# controller.net
KiCad netlist of a schematic drawn in EasyEDA Pro
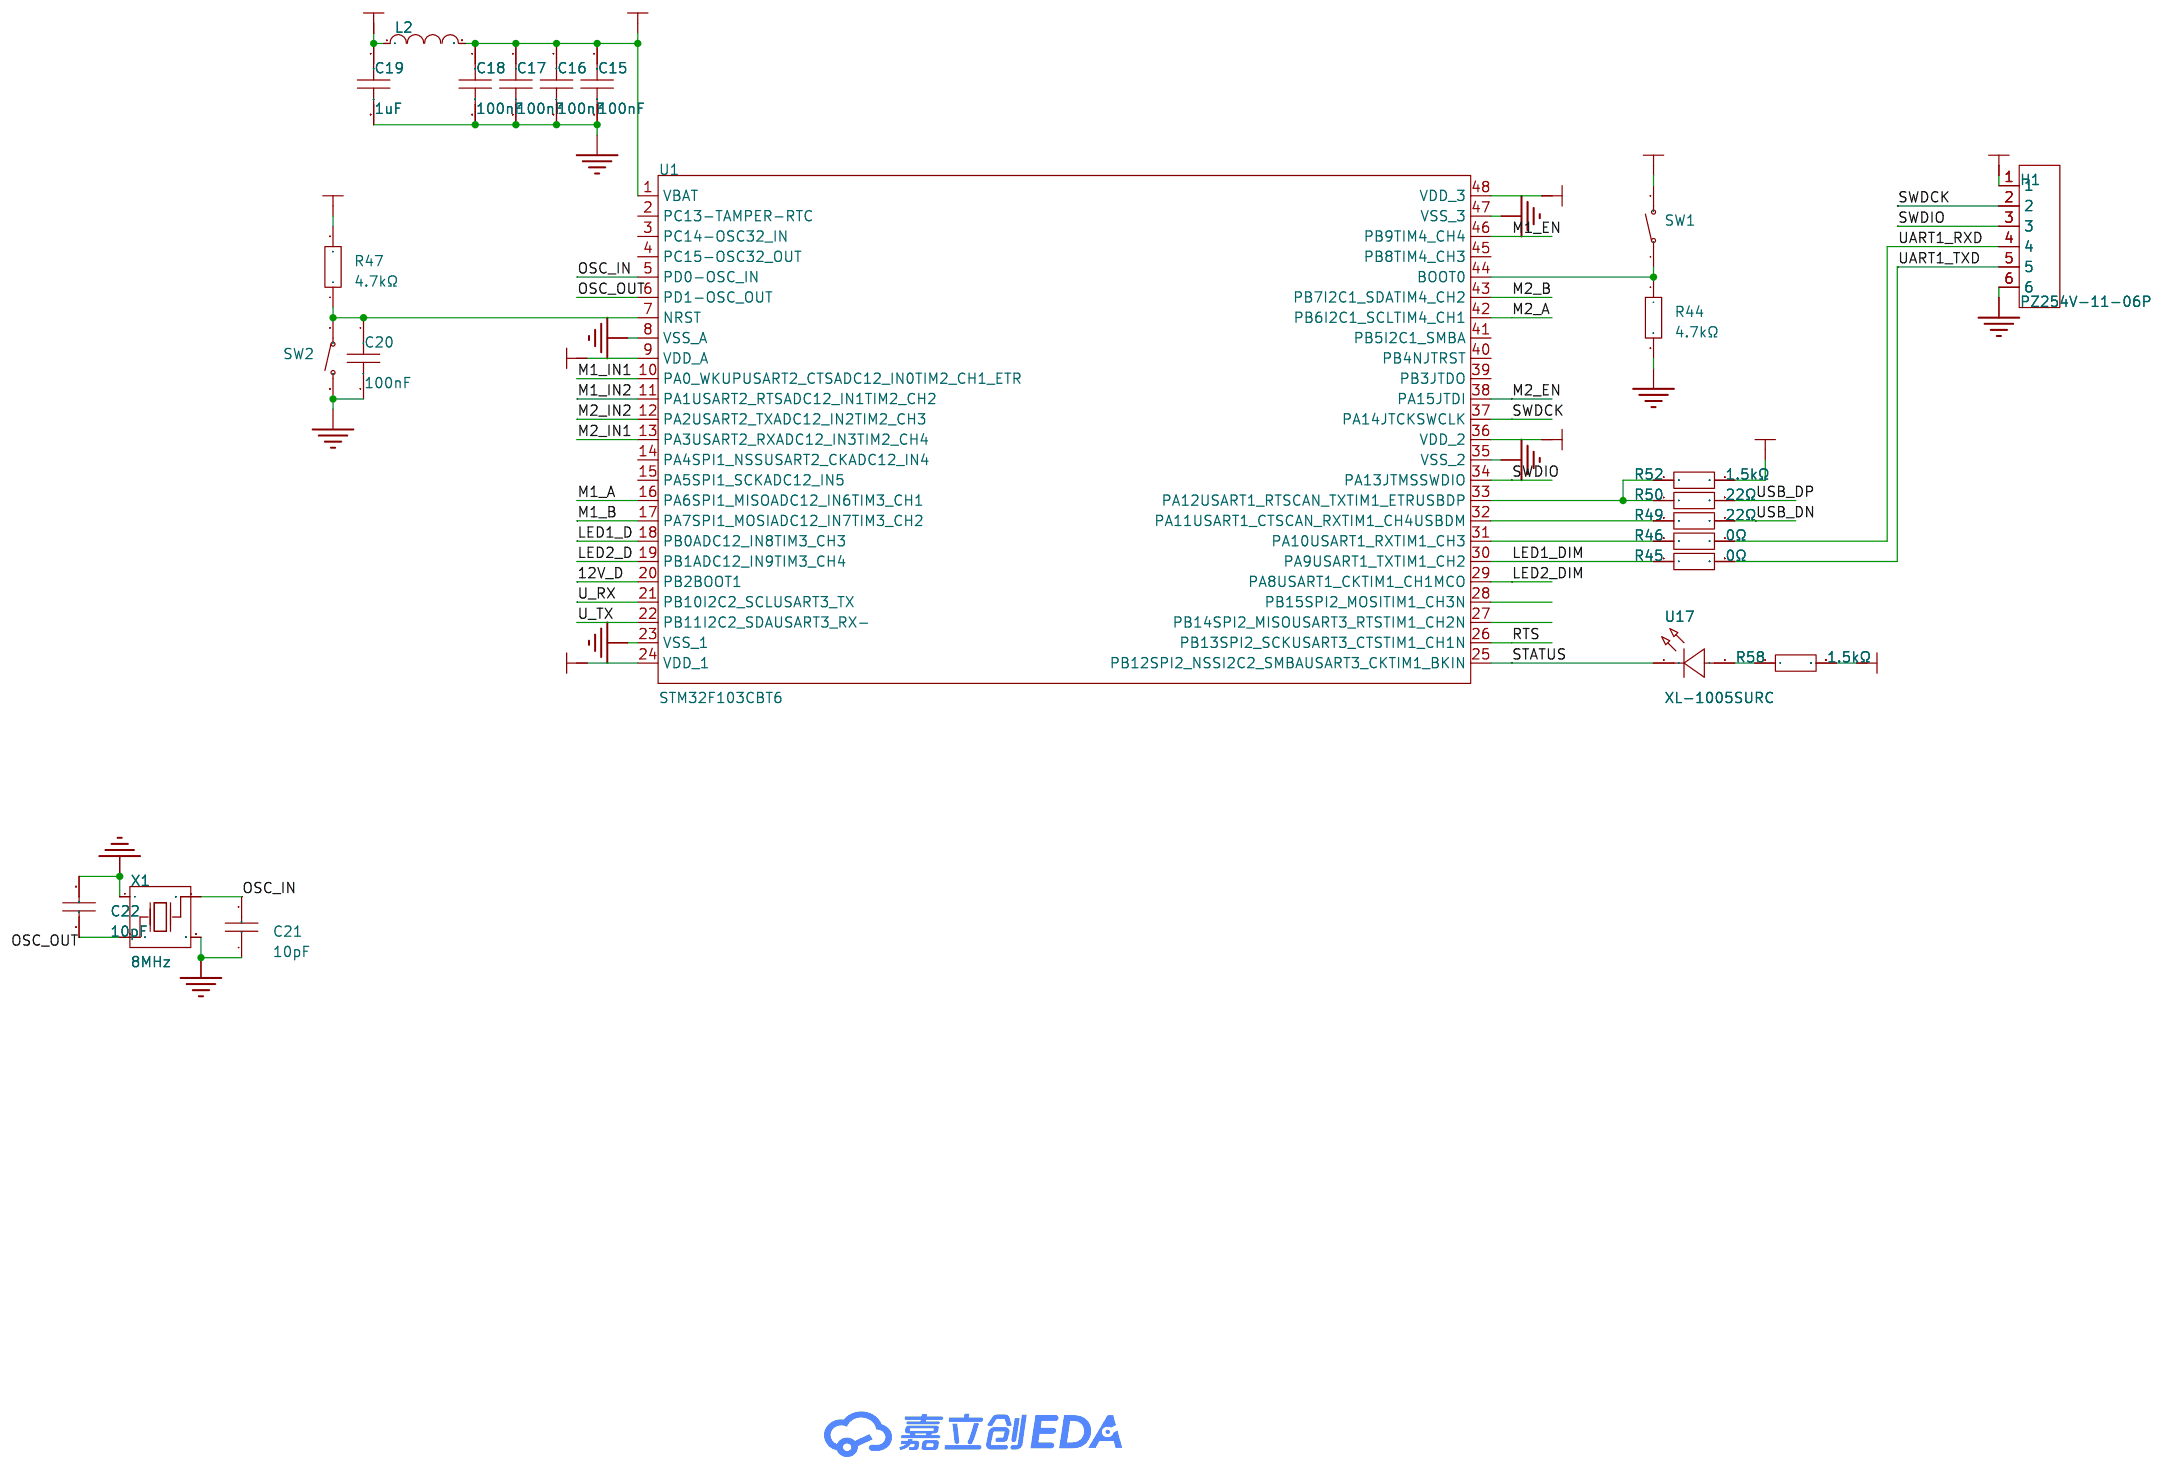
[diagram p0: mcu]
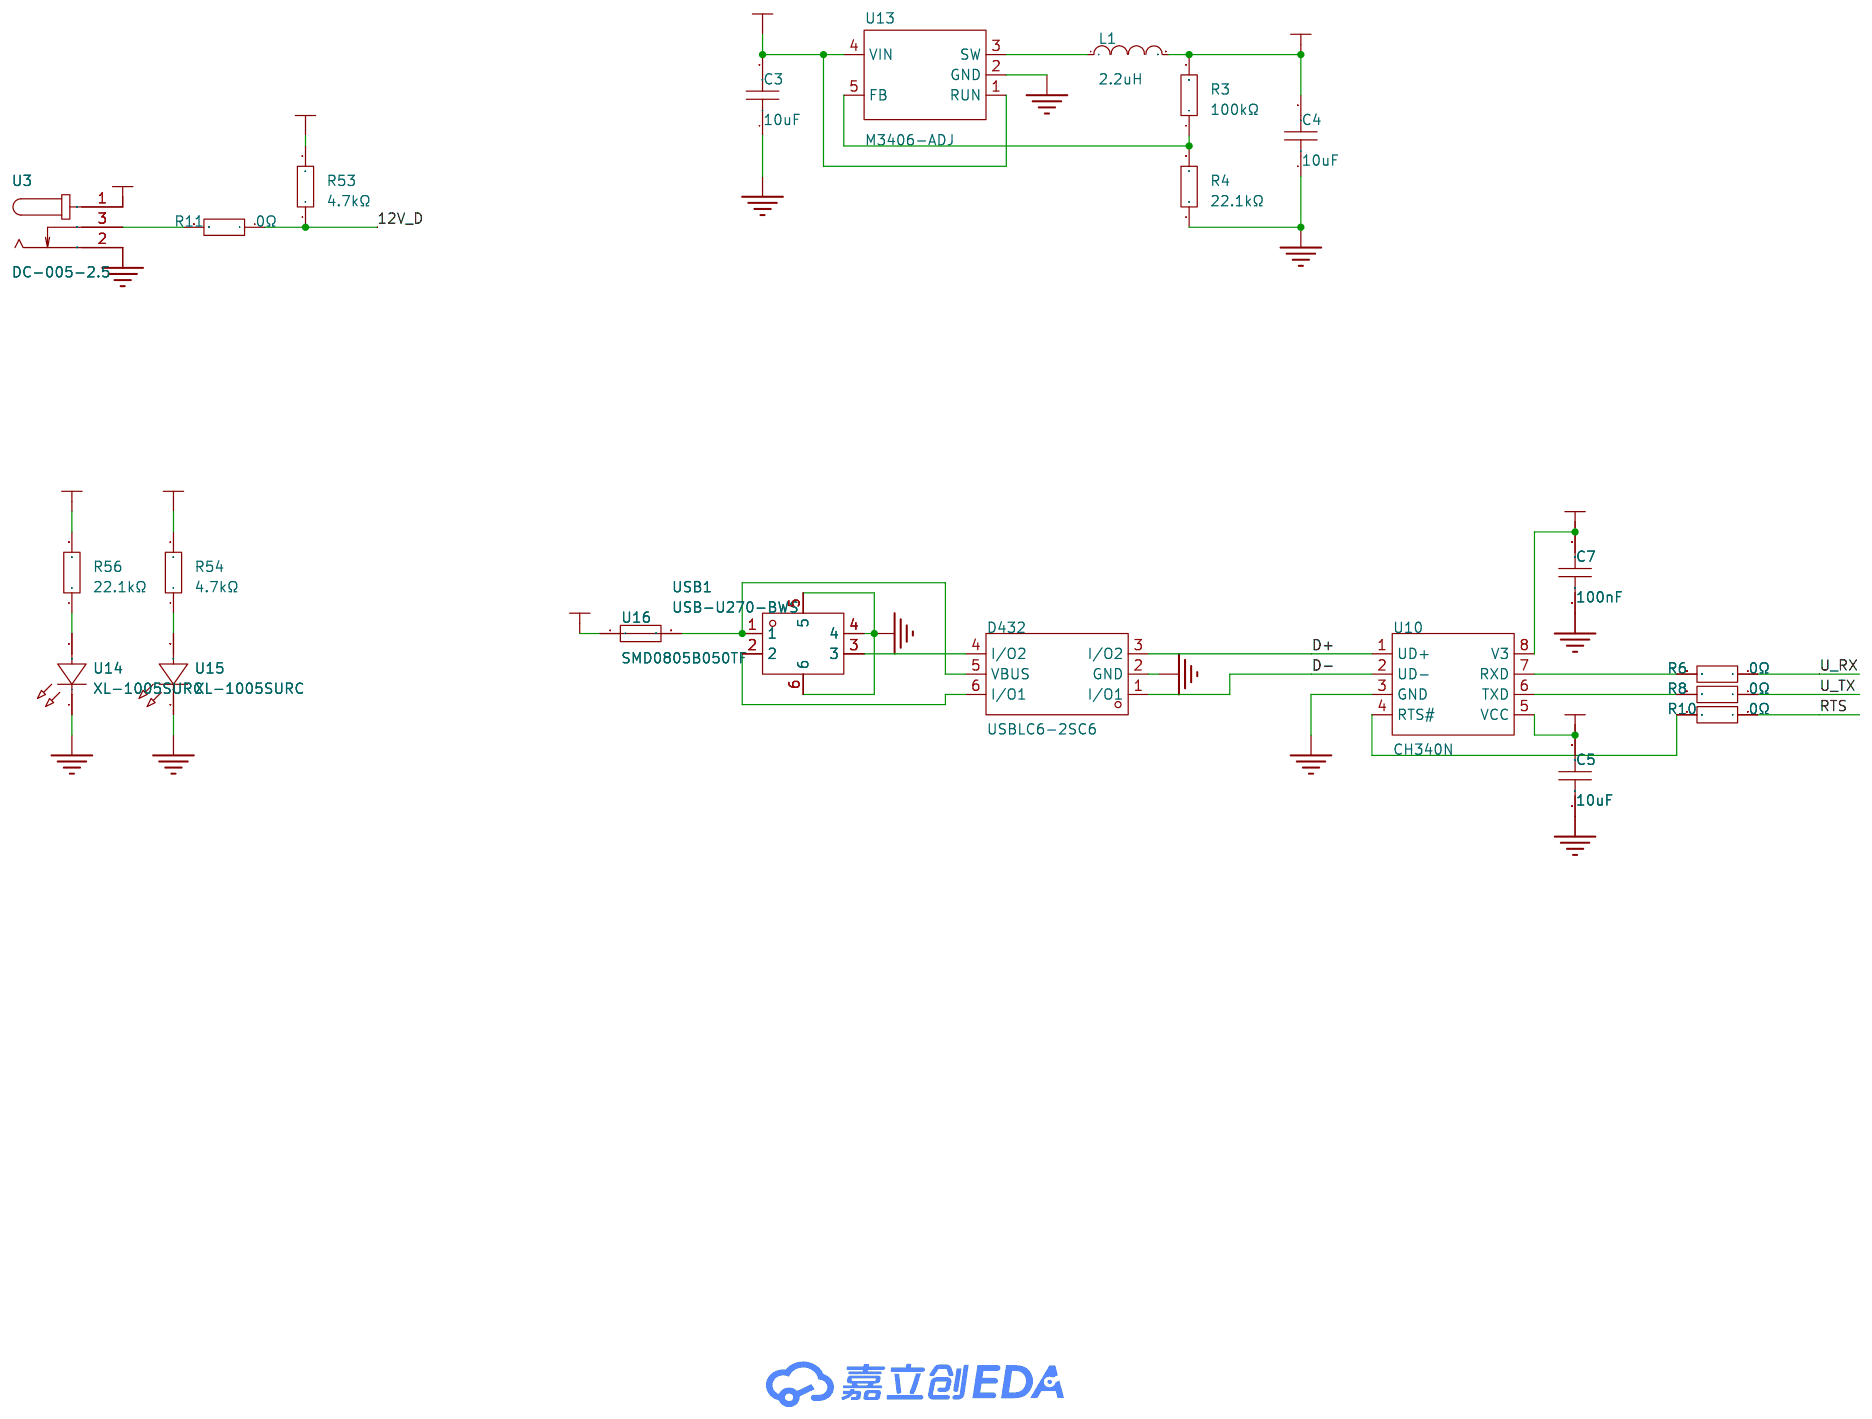
[diagram p1: power]
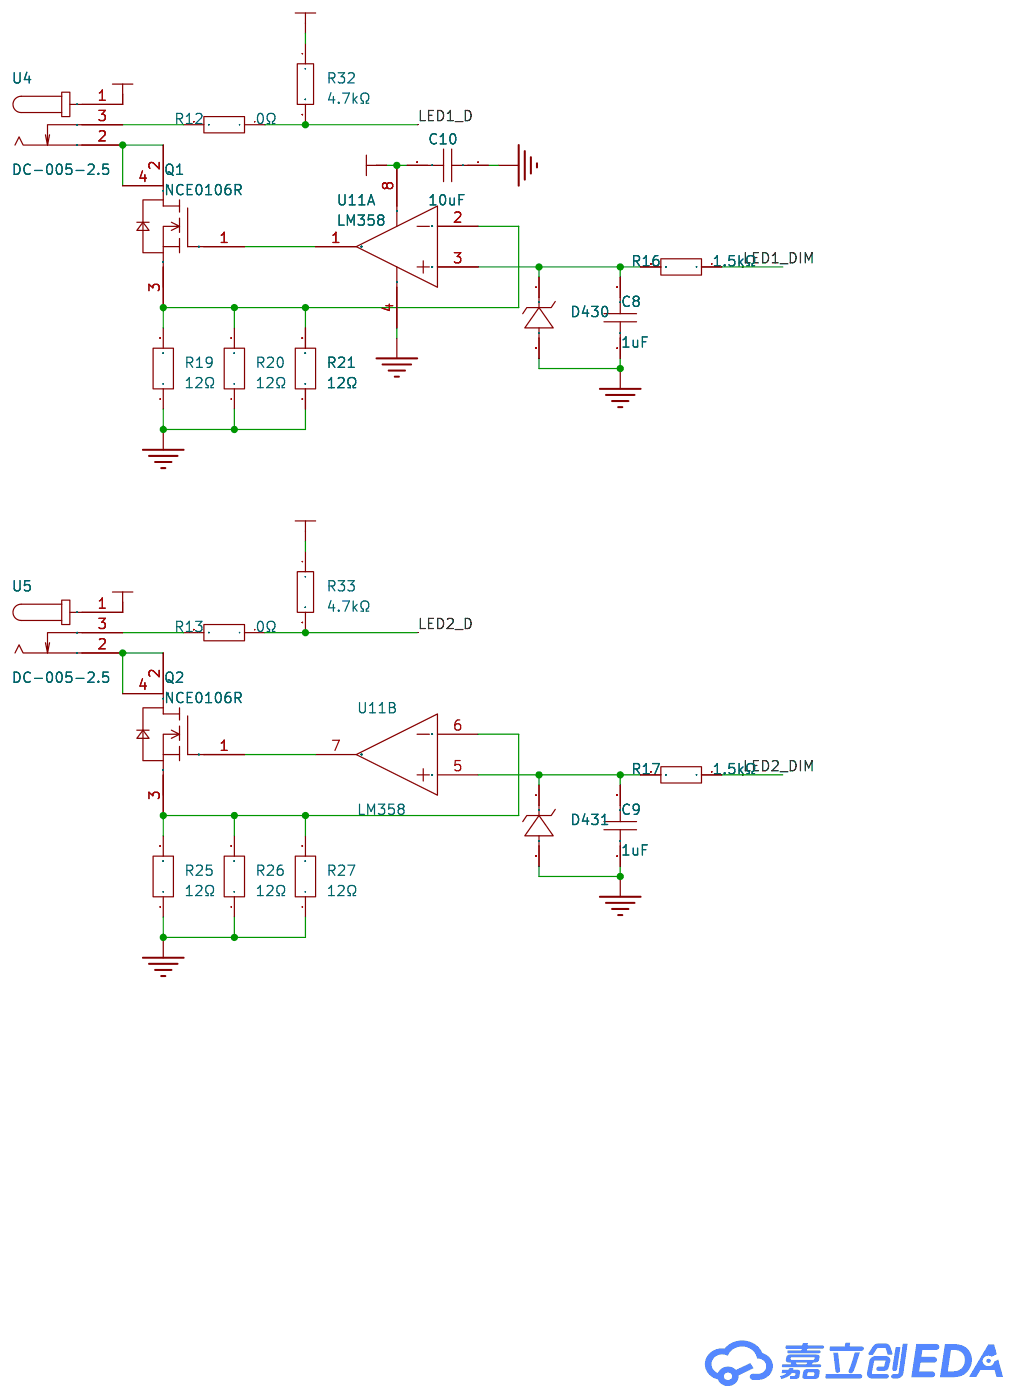
[diagram p2: led]
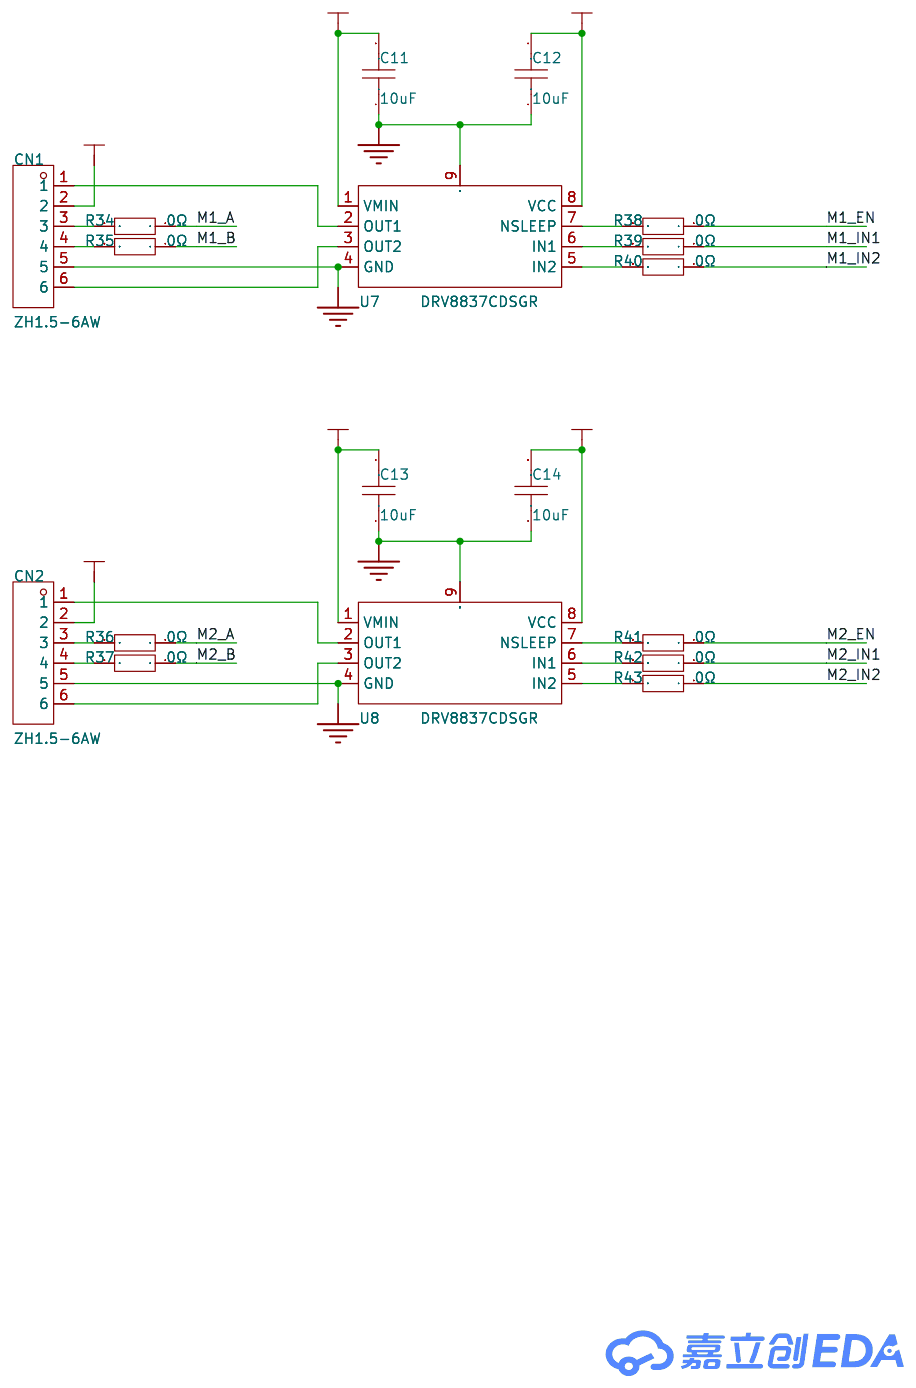
[diagram p3: motor]
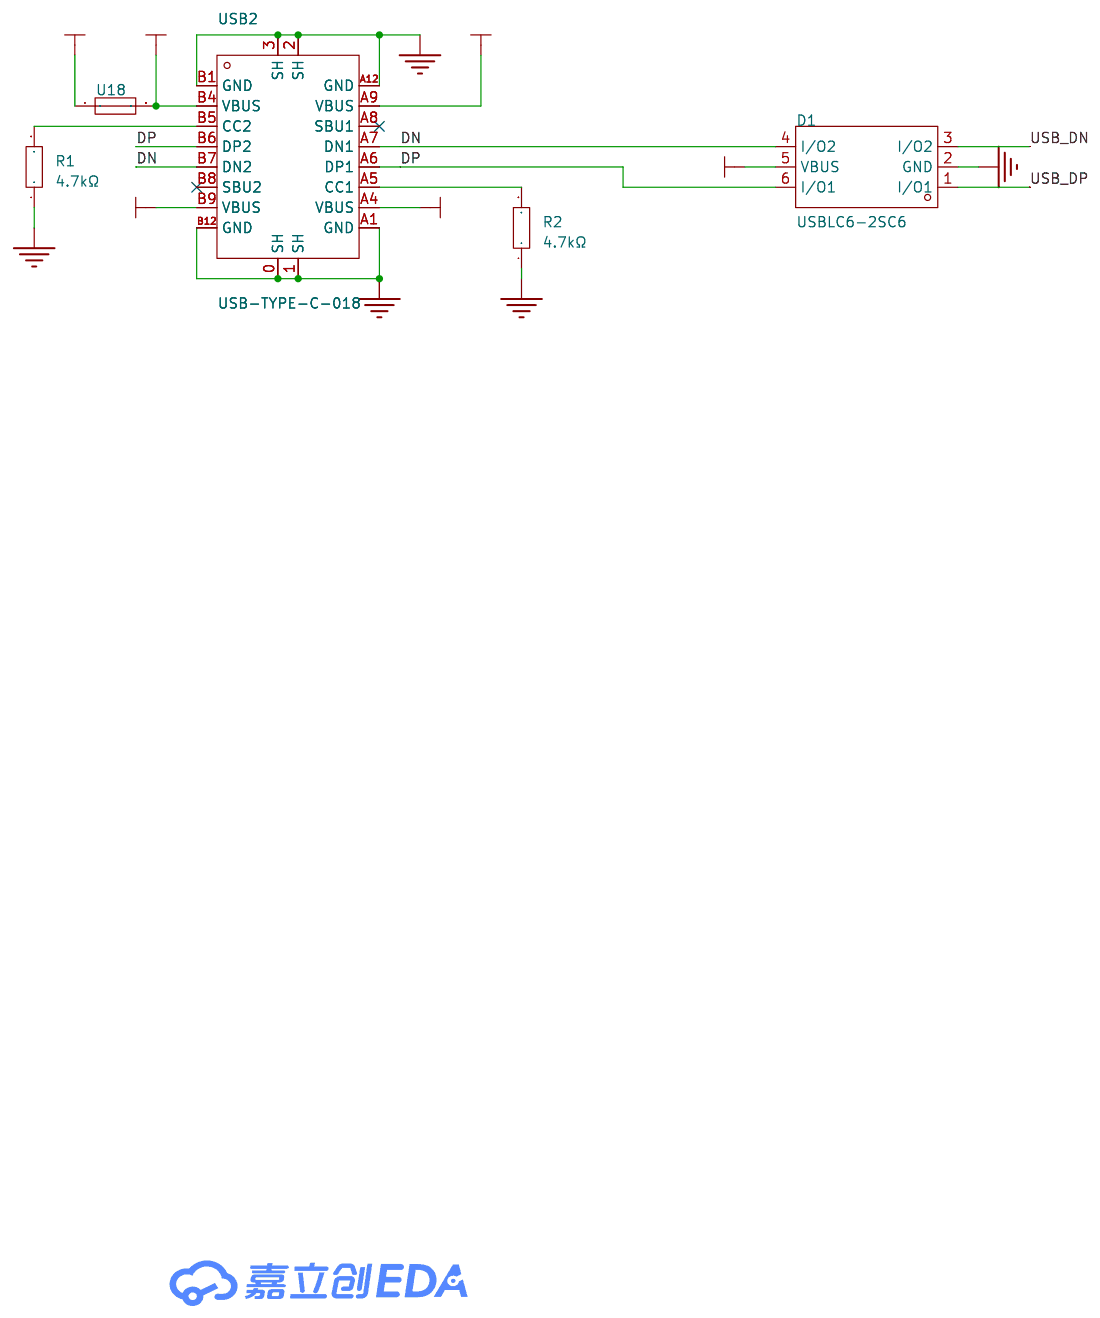
[diagram p4: typec]

(export (version "E")
  (design (tool "Eeschema 10.0.6"))
  (components
    (comp (ref "C15")
      (value "100nF")
      (footprint "easyedapro:C0603")
      (description "容值:100nF;精度:±20%;额定电压:25V;温度系数:X5R;")
      (fields
        (field (name "Manufacturer Part") "TCC0402X5R104M250AT")
        (field (name "Manufacturer") "CCTC(三环)")
      )
      (libsource (lib "easyedapro") (part "TCC0603X5R106K100CT"))
    )
    (comp (ref "C16")
      (value "100nF")
      (footprint "easyedapro:C0603")
      (description "容值:100nF;精度:±20%;额定电压:25V;温度系数:X5R;")
      (fields
        (field (name "Manufacturer Part") "TCC0402X5R104M250AT")
        (field (name "Manufacturer") "CCTC(三环)")
      )
      (libsource (lib "easyedapro") (part "TCC0603X5R106K100CT"))
    )
    (comp (ref "C17")
      (value "100nF")
      (footprint "easyedapro:C0603")
      (description "容值:100nF;精度:±20%;额定电压:25V;温度系数:X5R;")
      (fields
        (field (name "Manufacturer Part") "TCC0402X5R104M250AT")
        (field (name "Manufacturer") "CCTC(三环)")
      )
      (libsource (lib "easyedapro") (part "TCC0603X5R106K100CT"))
    )
    (comp (ref "C18")
      (value "100nF")
      (footprint "easyedapro:C0603")
      (description "容值:100nF;精度:±20%;额定电压:25V;温度系数:X5R;")
      (fields
        (field (name "Manufacturer Part") "TCC0402X5R104M250AT")
        (field (name "Manufacturer") "CCTC(三环)")
      )
      (libsource (lib "easyedapro") (part "TCC0603X5R106K100CT"))
    )
    (comp (ref "C19")
      (value "1uF")
      (footprint "easyedapro:C0603")
      (description "容值:10uF;精度:±10%;额定电压:10V;材质(温度系数):X5R;")
      (fields
        (field (name "Manufacturer Part") "TCC0402X5R105K100AT")
        (field (name "Manufacturer") "CCTC(三环)")
      )
      (libsource (lib "easyedapro") (part "TCC0603X5R106K100CT"))
    )
    (comp (ref "C20")
      (value "100nF")
      (footprint "easyedapro:C0603")
      (description "容值:100nF;精度:±20%;额定电压:25V;温度系数:X5R;")
      (fields
        (field (name "Manufacturer Part") "TCC0402X5R104M250AT")
        (field (name "Manufacturer") "CCTC(三环)")
      )
      (libsource (lib "easyedapro") (part "TCC0603X5R106K100CT"))
    )
    (comp (ref "C21")
      (value "10pF")
      (footprint "easyedapro:C0402")
      (description "容值:10pF;精度:±5%;额定电压:50V;材质(温度系数):NP0;")
      (fields
        (field (name "Manufacturer Part") "CC0402JRNPO9BN100")
        (field (name "Manufacturer") "YAGEO(国巨)")
      )
      (libsource (lib "easyedapro") (part "CC0402JRNPO9BN100"))
    )
    (comp (ref "C22")
      (value "10pF")
      (footprint "easyedapro:C0402")
      (description "容值:10pF;精度:±5%;额定电压:50V;材质(温度系数):NP0;")
      (fields
        (field (name "Manufacturer Part") "CC0402JRNPO9BN100")
        (field (name "Manufacturer") "YAGEO(国巨)")
      )
      (libsource (lib "easyedapro") (part "CC0402JRNPO9BN100"))
    )
    (comp (ref "H1")
      (value "PZ254V-11-06P")
      (footprint "easyedapro:HDR-TH_6P-P2.54-V-M")
      (fields (field (name "Manufacturer") "XFCN(兴飞)"))
      (libsource (lib "easyedapro") (part "PZ254V-11-06P"))
    )
    (comp (ref "L2")
      (value "GZ1005D102CTF")
      (footprint "easyedapro:L0402")
      (description "阻抗 @ 频率:1kΩ@100MHz;误差:±25%;直流电阻(DCR):700mΩ;")
      (fields (field (name "Manufacturer") "Sunlord(顺络)"))
      (libsource (lib "easyedapro") (part "GZ1005D102CTF"))
    )
    (comp (ref "R44")
      (value "4.7kΩ")
      (footprint "easyedapro:R0603")
      (description "电阻类型:厚膜电阻;阻值:0Ω;精度:±1%;功率:100mW;最大工作电压:75V;")
      (fields (field (name "Manufacturer Part") "RTT02472JTH") (field (name "Manufacturer") "RALEC(旺诠)"))
      (libsource (lib "easyedapro") (part "0603WAF0000T5E"))
    )
    (comp (ref "R45")
      (value "0Ω")
      (footprint "easyedapro:R0603")
      (description "电阻类型:厚膜电阻;阻值:0Ω;精度:±1%;功率:100mW;最大工作电压:75V;")
      (fields
        (field (name "Manufacturer Part") "0402WGF0000TCE")
        (field (name "Manufacturer") "UNI-ROYAL(厚声)")
      )
      (libsource (lib "easyedapro") (part "0603WAF0000T5E"))
    )
    (comp (ref "R46")
      (value "0Ω")
      (footprint "easyedapro:R0603")
      (description "电阻类型:厚膜电阻;阻值:0Ω;精度:±1%;功率:100mW;最大工作电压:75V;")
      (fields
        (field (name "Manufacturer Part") "0402WGF0000TCE")
        (field (name "Manufacturer") "UNI-ROYAL(厚声)")
      )
      (libsource (lib "easyedapro") (part "0603WAF0000T5E"))
    )
    (comp (ref "R47")
      (value "4.7kΩ")
      (footprint "easyedapro:R0603")
      (description "电阻类型:厚膜电阻;阻值:0Ω;精度:±1%;功率:100mW;最大工作电压:75V;")
      (fields (field (name "Manufacturer Part") "RTT02472JTH") (field (name "Manufacturer") "RALEC(旺诠)"))
      (libsource (lib "easyedapro") (part "0603WAF0000T5E"))
    )
    (comp (ref "R49")
      (value "22Ω")
      (footprint "easyedapro:R0402")
      (description "电阻类型:厚膜电阻;阻值:22Ω;精度:±1%;功率:62.5mW;最大工作电压:50V;温度系数:±100ppm/°C;")
      (fields
        (field (name "Manufacturer Part") "0402WGF220JTCE")
        (field (name "Manufacturer") "UNI-ROYAL(厚声)")
      )
      (libsource (lib "easyedapro") (part "0402WGF220JTCE"))
    )
    (comp (ref "R50")
      (value "22Ω")
      (footprint "easyedapro:R0402")
      (description "电阻类型:厚膜电阻;阻值:22Ω;精度:±1%;功率:62.5mW;最大工作电压:50V;温度系数:±100ppm/°C;")
      (fields
        (field (name "Manufacturer Part") "0402WGF220JTCE")
        (field (name "Manufacturer") "UNI-ROYAL(厚声)")
      )
      (libsource (lib "easyedapro") (part "0402WGF220JTCE"))
    )
    (comp (ref "R52")
      (value "1.5kΩ")
      (footprint "easyedapro:R0402")
      (description "电阻类型:厚膜电阻;阻值:1.5kΩ;精度:±1%;功率:62.5mW;最大工作电压:50V;温度系数:±100ppm/°C;")
      (fields
        (field (name "Manufacturer Part") "0402WGF1501TCE")
        (field (name "Manufacturer") "UNI-ROYAL(厚声)")
      )
      (libsource (lib "easyedapro") (part "0402WGF1501TCE"))
    )
    (comp (ref "R58")
      (value "1.5kΩ")
      (footprint "easyedapro:R0402")
      (description "电阻类型:厚膜电阻;阻值:1.5kΩ;精度:±1%;功率:62.5mW;最大工作电压:50V;温度系数:±100ppm/°C;")
      (fields
        (field (name "Manufacturer Part") "0402WGF1501TCE")
        (field (name "Manufacturer") "UNI-ROYAL(厚声)")
      )
      (libsource (lib "easyedapro") (part "0402WGF1501TCE"))
    )
    (comp (ref "SW1")
      (value "TS342A2P 160gf 021")
      (footprint "easyedapro:KEY-SMD_L3.9-W3.0-LS5.0")
      (fields (field (name "Manufacturer") "SHOU HAN(首韩)"))
      (libsource (lib "easyedapro") (part "TS342A2P 160GF 021"))
    )
    (comp (ref "SW2")
      (value "TS342A2P 160gf 021")
      (footprint "easyedapro:KEY-SMD_L3.9-W3.0-LS5.0")
      (fields (field (name "Manufacturer") "SHOU HAN(首韩)"))
      (libsource (lib "easyedapro") (part "TS342A2P 160GF 021"))
    )
    (comp (ref "U1")
      (value "STM32F103CBT6")
      (footprint "easyedapro:LQFP-48_L7.0-W7.0-P0.50-LS9.0-BL")
      (description "CPU内核:ARM-M3;CPU最大主频:72MHz;应用领域:-;")
      (fields (field (name "Manufacturer") "ST(意法半导体)"))
      (libsource (lib "easyedapro") (part "STM32F103CBT6"))
    )
    (comp (ref "U17")
      (value "XL-1005SURC")
      (footprint "easyedapro:LED0402-RD")
      (fields (field (name "Manufacturer") "XINGLIGHT(成兴光)"))
      (libsource (lib "easyedapro") (part "XL-1005SURC_C25503345"))
    )
    (comp (ref "X1")
      (value "8MHz")
      (footprint "easyedapro:CRYSTAL-SMD_4P-L3.2-W2.5-BL")
      (description "晶振类型:贴片晶振;频率:8MHz;常温频差:±10ppm;负载电容:10pF;频率稳定度:±15ppm;")
      (fields (field (name "Manufacturer Part") "TAXM8M4RDBCCT2T") (field (name "Manufacturer") "YJX(雅晶鑫)"))
      (libsource (lib "easyedapro") (part "TAXM8M4RDBCCT2T"))
    )
    (comp (ref "C3")
      (value "10uF")
      (footprint "easyedapro:C0603")
      (description "容值:10uF;精度:±10%;额定电压:10V;材质(温度系数):X5R;")
      (fields
        (field (name "Manufacturer Part") "TCC0603X5R106K100CT")
        (field (name "Manufacturer") "CCTC(三环)")
      )
      (libsource (lib "easyedapro") (part "TCC0603X5R106K100CT"))
    )
    (comp (ref "C4")
      (value "10uF")
      (footprint "easyedapro:C0603")
      (description "容值:10uF;精度:±10%;额定电压:10V;材质(温度系数):X5R;")
      (fields
        (field (name "Manufacturer Part") "TCC0603X5R106K100CT")
        (field (name "Manufacturer") "CCTC(三环)")
      )
      (libsource (lib "easyedapro") (part "TCC0603X5R106K100CT"))
    )
    (comp (ref "C5")
      (value "10uF")
      (footprint "easyedapro:C0603")
      (description "容值:10uF;精度:±10%;额定电压:10V;材质(温度系数):X5R;")
      (fields
        (field (name "Manufacturer Part") "TCC0603X5R106K100CT")
        (field (name "Manufacturer") "CCTC(三环)")
      )
      (libsource (lib "easyedapro") (part "TCC0603X5R106K100CT"))
    )
    (comp (ref "C7")
      (value "100nF")
      (footprint "easyedapro:C0603")
      (description "容值:100nF;精度:±20%;额定电压:25V;温度系数:X5R;")
      (fields
        (field (name "Manufacturer Part") "TCC0402X5R104M250AT")
        (field (name "Manufacturer") "CCTC(三环)")
      )
      (libsource (lib "easyedapro") (part "TCC0603X5R106K100CT"))
    )
    (comp (ref "D432")
      (value "USBLC6-2SC6")
      (footprint "easyedapro:SOT-23-6_L2.9-W1.6-P0.95-LS2.8-BL")
      (description "最大钳位电压:15V;击穿电压:6V;")
      (fields (field (name "Manufacturer") "UMW(友台半导体)"))
      (libsource (lib "easyedapro") (part "USBLC6-2SC6_C2687116"))
    )
    (comp (ref "L1")
      (value "2.2uH")
      (footprint "easyedapro:IND-SMD_L2.0-W1.6_WPN2016X")
      (description "电感值:2.2uH;精度:±20%;额定电流:1.45A;饱和电流(Isat):2.15A;类型:-;")
      (fields
        (field (name "Manufacturer Part") "WPN201610H2R2MT")
        (field (name "Manufacturer") "Sunlord(顺络)")
      )
      (libsource (lib "easyedapro") (part "WPN201610H2R2MT"))
    )
    (comp (ref "R3")
      (value "100kΩ")
      (footprint "easyedapro:R0402")
      (description "电阻类型:厚膜电阻;阻值:100kΩ;精度:±1%;功率:62.5mW;最大工作电压:50V;温度系数:±100ppm/°C;")
      (fields (field (name "Manufacturer Part") "RTT021003FTH") (field (name "Manufacturer") "RALEC(旺诠)"))
      (libsource (lib "easyedapro") (part "RTT021003FTH"))
    )
    (comp (ref "R4")
      (value "22.1kΩ")
      (footprint "easyedapro:R0402")
      (description "电阻类型:厚膜电阻;阻值:22.1kΩ;精度:±1%;功率:62.5mW;最大工作电压:50V;温度系数:±100ppm/°C;")
      (fields
        (field (name "Manufacturer Part") "0402WGF2212TCE")
        (field (name "Manufacturer") "UNI-ROYAL(厚声)")
      )
      (libsource (lib "easyedapro") (part "0402WGF2212TCE"))
    )
    (comp (ref "R6")
      (value "0Ω")
      (footprint "easyedapro:R0603")
      (description "电阻类型:厚膜电阻;阻值:0Ω;精度:±1%;功率:100mW;最大工作电压:75V;")
      (fields
        (field (name "Manufacturer Part") "0402WGF0000TCE")
        (field (name "Manufacturer") "UNI-ROYAL(厚声)")
      )
      (libsource (lib "easyedapro") (part "0603WAF0000T5E"))
    )
    (comp (ref "R8")
      (value "0Ω")
      (footprint "easyedapro:R0603")
      (description "电阻类型:厚膜电阻;阻值:0Ω;精度:±1%;功率:100mW;最大工作电压:75V;")
      (fields
        (field (name "Manufacturer Part") "0402WGF0000TCE")
        (field (name "Manufacturer") "UNI-ROYAL(厚声)")
      )
      (libsource (lib "easyedapro") (part "0603WAF0000T5E"))
    )
    (comp (ref "R10")
      (value "0Ω")
      (footprint "easyedapro:R0603")
      (description "电阻类型:厚膜电阻;阻值:0Ω;精度:±1%;功率:100mW;最大工作电压:75V;")
      (fields
        (field (name "Manufacturer Part") "0402WGF0000TCE")
        (field (name "Manufacturer") "UNI-ROYAL(厚声)")
      )
      (libsource (lib "easyedapro") (part "0603WAF0000T5E"))
    )
    (comp (ref "R11")
      (value "0Ω")
      (footprint "easyedapro:R0603")
      (description "电阻类型:厚膜电阻;阻值:0Ω;精度:±1%;功率:100mW;最大工作电压:75V;")
      (fields
        (field (name "Manufacturer Part") "0402WGF0000TCE")
        (field (name "Manufacturer") "UNI-ROYAL(厚声)")
      )
      (libsource (lib "easyedapro") (part "0603WAF0000T5E"))
    )
    (comp (ref "R53")
      (value "4.7kΩ")
      (footprint "easyedapro:R0603")
      (description "电阻类型:厚膜电阻;阻值:0Ω;精度:±1%;功率:100mW;最大工作电压:75V;")
      (fields (field (name "Manufacturer Part") "RTT02472JTH") (field (name "Manufacturer") "RALEC(旺诠)"))
      (libsource (lib "easyedapro") (part "0603WAF0000T5E"))
    )
    (comp (ref "R54")
      (value "4.7kΩ")
      (footprint "easyedapro:R0603")
      (description "电阻类型:厚膜电阻;阻值:0Ω;精度:±1%;功率:100mW;最大工作电压:75V;")
      (fields (field (name "Manufacturer Part") "RTT02472JTH") (field (name "Manufacturer") "RALEC(旺诠)"))
      (libsource (lib "easyedapro") (part "0603WAF0000T5E"))
    )
    (comp (ref "R56")
      (value "22.1kΩ")
      (footprint "easyedapro:R0402")
      (description "电阻类型:厚膜电阻;阻值:22.1kΩ;精度:±1%;功率:62.5mW;最大工作电压:50V;温度系数:±100ppm/°C;")
      (fields
        (field (name "Manufacturer Part") "0402WGF2212TCE")
        (field (name "Manufacturer") "UNI-ROYAL(厚声)")
      )
      (libsource (lib "easyedapro") (part "0402WGF2212TCE"))
    )
    (comp (ref "U3")
      (value "DC-005-2.5")
      (footprint "easyedapro:DC-IN-TH_DC-005-2.0_C22459640")
      (description "连接器类型:DC电源插座;安装方式:弯插;触点内径:2mm;触点外径:6.3mm;")
      (fields (field (name "Manufacturer") "HanElectricity(瀚源)"))
      (libsource (lib "easyedapro") (part "DC-005-2.0_C22459640"))
    )
    (comp (ref "U10")
      (value "CH340N")
      (footprint "easyedapro:SOP-8_L4.9-W3.9-P1.27-LS6.0-BL")
      (description "应用功能:USB转串口;接口协议:USB 2.0;通道数:1;数据速率:2Mbps;")
      (fields (field (name "Manufacturer") "WCH(南京沁恒)"))
      (libsource (lib "easyedapro") (part "CH340N_C2977777"))
    )
    (comp (ref "U13")
      (value "M3406-ADJ")
      (footprint "easyedapro:SOT-23-5_L3.0-W1.7-P0.95-LS2.8-BR")
      (description "功能类型:降压型;输出类型:可调;工作电压:2V~6V;输出电流:800mA;")
      (fields (field (name "Manufacturer") "西安航天民芯"))
      (libsource (lib "easyedapro") (part "M3406"))
    )
    (comp (ref "U14")
      (value "XL-1005SURC")
      (footprint "easyedapro:LED0402-RD")
      (fields (field (name "Manufacturer") "XINGLIGHT(成兴光)"))
      (libsource (lib "easyedapro") (part "XL-1005SURC_C25503345"))
    )
    (comp (ref "U15")
      (value "XL-1005SURC")
      (footprint "easyedapro:LED0402-RD")
      (fields (field (name "Manufacturer") "XINGLIGHT(成兴光)"))
      (libsource (lib "easyedapro") (part "XL-1005SURC_C25503345"))
    )
    (comp (ref "U16")
      (value "SMD0805B050TF")
      (footprint "easyedapro:F0805")
      (description "耐压:6V;最大电流:100A;保持电流(Ih):500mA;跳闸电流:1A;")
      (fields (field (name "Manufacturer") "Brightking(君耀电子)"))
      (libsource (lib "easyedapro") (part "SMD0805B050TF"))
    )
    (comp (ref "USB1")
      (value "USB-U270-BWS")
      (footprint "easyedapro:USB-TH_U270-BWS")
      (description "连接器类型:Type-B;标准:USB 2.0;公母:母;安装方式:弯插;触点数量:4P;端口数量:1;额定电流 - 电源:-;工作温度范围:-;")
      (fields (field (name "Manufacturer") "HANBO(汉博)"))
      (libsource (lib "easyedapro") (part "USB-U270-BWS"))
    )
    (comp (ref "C8")
      (value "1uF")
      (footprint "easyedapro:C0603")
      (description "容值:10uF;精度:±10%;额定电压:10V;材质(温度系数):X5R;")
      (fields
        (field (name "Manufacturer Part") "TCC0402X5R105K100AT")
        (field (name "Manufacturer") "CCTC(三环)")
      )
      (libsource (lib "easyedapro") (part "TCC0603X5R106K100CT"))
    )
    (comp (ref "C9")
      (value "1uF")
      (footprint "easyedapro:C0603")
      (description "容值:10uF;精度:±10%;额定电压:10V;材质(温度系数):X5R;")
      (fields
        (field (name "Manufacturer Part") "TCC0402X5R105K100AT")
        (field (name "Manufacturer") "CCTC(三环)")
      )
      (libsource (lib "easyedapro") (part "TCC0603X5R106K100CT"))
    )
    (comp (ref "C10")
      (value "10uF")
      (footprint "easyedapro:C0603")
      (description "容值:10uF;精度:±10%;额定电压:10V;材质(温度系数):X5R;")
      (fields
        (field (name "Manufacturer Part") "TCC0603X5R106K100CT")
        (field (name "Manufacturer") "CCTC(三环)")
      )
      (libsource (lib "easyedapro") (part "TCC0603X5R106K100CT"))
    )
    (comp (ref "D430")
      (value "ZMM3V3")
      (footprint "easyedapro:LL-34_L3.5-W1.5-RD")
      (description "二极管配置:独立式;稳压值(标称值):3.3V;稳压值(范围):3.1V~3.5V;功率(Pd):500mW;")
      (fields (field (name "Manufacturer") "HXY MOSFET(华轩阳电子)"))
      (libsource (lib "easyedapro") (part "ZMM3V3_C5345987"))
    )
    (comp (ref "D431")
      (value "ZMM3V3")
      (footprint "easyedapro:LL-34_L3.5-W1.5-RD")
      (description "二极管配置:独立式;稳压值(标称值):3.3V;稳压值(范围):3.1V~3.5V;功率(Pd):500mW;")
      (fields (field (name "Manufacturer") "HXY MOSFET(华轩阳电子)"))
      (libsource (lib "easyedapro") (part "ZMM3V3_C5345987"))
    )
    (comp (ref "Q1")
      (value "NCE0106R")
      (footprint "easyedapro:SOT-223_L6.5-W3.5-P2.30-LS7.0-BR")
      (description "类型:1个N沟道;漏源电压(Vdss):100V;连续漏极电流(Id):6A;导通电阻(RDS(on)):140mΩ@10V,5A;耗散功率(Pd):3W;阈值电压(Vgs(th)):2.5V;")
      (fields (field (name "Manufacturer") "NCE(无锡新洁能)"))
      (libsource (lib "easyedapro") (part "NCE0106R"))
    )
    (comp (ref "Q2")
      (value "NCE0106R")
      (footprint "easyedapro:SOT-223_L6.5-W3.5-P2.30-LS7.0-BR")
      (description "类型:1个N沟道;漏源电压(Vdss):100V;连续漏极电流(Id):6A;导通电阻(RDS(on)):140mΩ@10V,5A;耗散功率(Pd):3W;阈值电压(Vgs(th)):2.5V;")
      (fields (field (name "Manufacturer") "NCE(无锡新洁能)"))
      (libsource (lib "easyedapro") (part "NCE0106R"))
    )
    (comp (ref "R12")
      (value "0Ω")
      (footprint "easyedapro:R0603")
      (description "电阻类型:厚膜电阻;阻值:0Ω;精度:±1%;功率:100mW;最大工作电压:75V;")
      (fields
        (field (name "Manufacturer Part") "0402WGF0000TCE")
        (field (name "Manufacturer") "UNI-ROYAL(厚声)")
      )
      (libsource (lib "easyedapro") (part "0603WAF0000T5E"))
    )
    (comp (ref "R13")
      (value "0Ω")
      (footprint "easyedapro:R0603")
      (description "电阻类型:厚膜电阻;阻值:0Ω;精度:±1%;功率:100mW;最大工作电压:75V;")
      (fields
        (field (name "Manufacturer Part") "0402WGF0000TCE")
        (field (name "Manufacturer") "UNI-ROYAL(厚声)")
      )
      (libsource (lib "easyedapro") (part "0603WAF0000T5E"))
    )
    (comp (ref "R16")
      (value "1.5kΩ")
      (footprint "easyedapro:R0603")
      (description "电阻类型:厚膜电阻;阻值:0Ω;精度:±1%;功率:100mW;最大工作电压:75V;")
      (fields
        (field (name "Manufacturer Part") "0402WGF1501TCE")
        (field (name "Manufacturer") "UNI-ROYAL(厚声)")
      )
      (libsource (lib "easyedapro") (part "0603WAF0000T5E"))
    )
    (comp (ref "R17")
      (value "1.5kΩ")
      (footprint "easyedapro:R0603")
      (description "电阻类型:厚膜电阻;阻值:0Ω;精度:±1%;功率:100mW;最大工作电压:75V;")
      (fields
        (field (name "Manufacturer Part") "0402WGF1501TCE")
        (field (name "Manufacturer") "UNI-ROYAL(厚声)")
      )
      (libsource (lib "easyedapro") (part "0603WAF0000T5E"))
    )
    (comp (ref "R19")
      (value "12Ω")
      (footprint "easyedapro:R2512")
      (description "电阻类型:厚膜电阻;阻值:12Ω;精度:±1%;功率:2W;温度系数:±200ppm/°C;")
      (fields (field (name "Manufacturer Part") "RC2512FK-7W12RL") (field (name "Manufacturer") "YAGEO(国巨)"))
      (libsource (lib "easyedapro") (part "RC2512FK-7W12RL"))
    )
    (comp (ref "R20")
      (value "12Ω")
      (footprint "easyedapro:R2512")
      (description "电阻类型:厚膜电阻;阻值:12Ω;精度:±1%;功率:2W;温度系数:±200ppm/°C;")
      (fields (field (name "Manufacturer Part") "RC2512FK-7W12RL") (field (name "Manufacturer") "YAGEO(国巨)"))
      (libsource (lib "easyedapro") (part "RC2512FK-7W12RL"))
    )
    (comp (ref "R21")
      (value "12Ω")
      (footprint "easyedapro:R2512")
      (description "电阻类型:厚膜电阻;阻值:12Ω;精度:±1%;功率:2W;温度系数:±200ppm/°C;")
      (fields (field (name "Manufacturer Part") "RC2512FK-7W12RL") (field (name "Manufacturer") "YAGEO(国巨)"))
      (libsource (lib "easyedapro") (part "RC2512FK-7W12RL"))
    )
    (comp (ref "R25")
      (value "12Ω")
      (footprint "easyedapro:R2512")
      (description "电阻类型:厚膜电阻;阻值:12Ω;精度:±1%;功率:2W;温度系数:±200ppm/°C;")
      (fields (field (name "Manufacturer Part") "RC2512FK-7W12RL") (field (name "Manufacturer") "YAGEO(国巨)"))
      (libsource (lib "easyedapro") (part "RC2512FK-7W12RL"))
    )
    (comp (ref "R26")
      (value "12Ω")
      (footprint "easyedapro:R2512")
      (description "电阻类型:厚膜电阻;阻值:12Ω;精度:±1%;功率:2W;温度系数:±200ppm/°C;")
      (fields (field (name "Manufacturer Part") "RC2512FK-7W12RL") (field (name "Manufacturer") "YAGEO(国巨)"))
      (libsource (lib "easyedapro") (part "RC2512FK-7W12RL"))
    )
    (comp (ref "R27")
      (value "12Ω")
      (footprint "easyedapro:R2512")
      (description "电阻类型:厚膜电阻;阻值:12Ω;精度:±1%;功率:2W;温度系数:±200ppm/°C;")
      (fields (field (name "Manufacturer Part") "RC2512FK-7W12RL") (field (name "Manufacturer") "YAGEO(国巨)"))
      (libsource (lib "easyedapro") (part "RC2512FK-7W12RL"))
    )
    (comp (ref "R32")
      (value "4.7kΩ")
      (footprint "easyedapro:R0603")
      (description "电阻类型:厚膜电阻;阻值:0Ω;精度:±1%;功率:100mW;最大工作电压:75V;")
      (fields (field (name "Manufacturer Part") "RTT02472JTH") (field (name "Manufacturer") "RALEC(旺诠)"))
      (libsource (lib "easyedapro") (part "0603WAF0000T5E"))
    )
    (comp (ref "R33")
      (value "4.7kΩ")
      (footprint "easyedapro:R0603")
      (description "电阻类型:厚膜电阻;阻值:0Ω;精度:±1%;功率:100mW;最大工作电压:75V;")
      (fields (field (name "Manufacturer Part") "RTT02472JTH") (field (name "Manufacturer") "RALEC(旺诠)"))
      (libsource (lib "easyedapro") (part "0603WAF0000T5E"))
    )
    (comp (ref "U4")
      (value "DC-005-2.5")
      (footprint "easyedapro:DC-IN-TH_DC-005-2.0_C22459640")
      (description "连接器类型:DC电源插座;安装方式:弯插;触点内径:2mm;触点外径:6.3mm;")
      (fields (field (name "Manufacturer") "HanElectricity(瀚源)"))
      (libsource (lib "easyedapro") (part "DC-005-2.0_C22459640"))
    )
    (comp (ref "U5")
      (value "DC-005-2.5")
      (footprint "easyedapro:DC-IN-TH_DC-005-2.0_C22459640")
      (description "连接器类型:DC电源插座;安装方式:弯插;触点内径:2mm;触点外径:6.3mm;")
      (fields (field (name "Manufacturer") "HanElectricity(瀚源)"))
      (libsource (lib "easyedapro") (part "DC-005-2.0_C22459640"))
    )
    (comp (ref "U11")
      (value "LM358")
      (footprint "easyedapro:SOIC-8_L4.9-W3.9-P1.27-LS6.0-BL")
      (description "放大器数:双路;轨到轨:-;增益带宽积(GBP):1.2MHz;输入失调电压(Vos):5mV;压摆率(SR):-;输入偏置电流(Ib):50nA;")
      (fields (field (name "Manufacturer") "GR(国睿)"))
      (libsource (lib "easyedapro") (part "LM358_C18164495"))
    )
    (comp (ref "C11")
      (value "10uF")
      (footprint "easyedapro:C0603")
      (description "容值:10uF;精度:±10%;额定电压:10V;材质(温度系数):X5R;")
      (fields
        (field (name "Manufacturer Part") "TCC0603X5R106K100CT")
        (field (name "Manufacturer") "CCTC(三环)")
      )
      (libsource (lib "easyedapro") (part "TCC0603X5R106K100CT"))
    )
    (comp (ref "C12")
      (value "10uF")
      (footprint "easyedapro:C0603")
      (description "容值:10uF;精度:±10%;额定电压:10V;材质(温度系数):X5R;")
      (fields
        (field (name "Manufacturer Part") "TCC0603X5R106K100CT")
        (field (name "Manufacturer") "CCTC(三环)")
      )
      (libsource (lib "easyedapro") (part "TCC0603X5R106K100CT"))
    )
    (comp (ref "C13")
      (value "10uF")
      (footprint "easyedapro:C0603")
      (description "容值:10uF;精度:±10%;额定电压:10V;材质(温度系数):X5R;")
      (fields
        (field (name "Manufacturer Part") "TCC0603X5R106K100CT")
        (field (name "Manufacturer") "CCTC(三环)")
      )
      (libsource (lib "easyedapro") (part "TCC0603X5R106K100CT"))
    )
    (comp (ref "C14")
      (value "10uF")
      (footprint "easyedapro:C0603")
      (description "容值:10uF;精度:±10%;额定电压:10V;材质(温度系数):X5R;")
      (fields
        (field (name "Manufacturer Part") "TCC0603X5R106K100CT")
        (field (name "Manufacturer") "CCTC(三环)")
      )
      (libsource (lib "easyedapro") (part "TCC0603X5R106K100CT"))
    )
    (comp (ref "CN1")
      (value "ZH1.5-6AW")
      (footprint "easyedapro:CONN-TH_ZH1.5-6AW")
      (description "插针结构:1x6P;间距:1.5mm;安装方式:弯插;参考系列:ZH;总PIN数:6P;排数:1;每排PIN数:6;行距:-;额定电流:1A;工作温度范围:-25°C~+85°C;")
      (fields (field (name "Manufacturer") "CAX(创都)"))
      (libsource (lib "easyedapro") (part "ZH1.5-6AW_C722927"))
    )
    (comp (ref "CN2")
      (value "ZH1.5-6AW")
      (footprint "easyedapro:CONN-TH_ZH1.5-6AW")
      (description "插针结构:1x6P;间距:1.5mm;安装方式:弯插;参考系列:ZH;总PIN数:6P;排数:1;每排PIN数:6;行距:-;额定电流:1A;工作温度范围:-25°C~+85°C;")
      (fields (field (name "Manufacturer") "CAX(创都)"))
      (libsource (lib "easyedapro") (part "ZH1.5-6AW_C722927"))
    )
    (comp (ref "R34")
      (value "0Ω")
      (footprint "easyedapro:R0603")
      (description "电阻类型:厚膜电阻;阻值:0Ω;精度:±1%;功率:100mW;最大工作电压:75V;")
      (fields
        (field (name "Manufacturer Part") "0402WGF0000TCE")
        (field (name "Manufacturer") "UNI-ROYAL(厚声)")
      )
      (libsource (lib "easyedapro") (part "0603WAF0000T5E"))
    )
    (comp (ref "R35")
      (value "0Ω")
      (footprint "easyedapro:R0603")
      (description "电阻类型:厚膜电阻;阻值:0Ω;精度:±1%;功率:100mW;最大工作电压:75V;")
      (fields
        (field (name "Manufacturer Part") "0402WGF0000TCE")
        (field (name "Manufacturer") "UNI-ROYAL(厚声)")
      )
      (libsource (lib "easyedapro") (part "0603WAF0000T5E"))
    )
    (comp (ref "R36")
      (value "0Ω")
      (footprint "easyedapro:R0603")
      (description "电阻类型:厚膜电阻;阻值:0Ω;精度:±1%;功率:100mW;最大工作电压:75V;")
      (fields
        (field (name "Manufacturer Part") "0402WGF0000TCE")
        (field (name "Manufacturer") "UNI-ROYAL(厚声)")
      )
      (libsource (lib "easyedapro") (part "0603WAF0000T5E"))
    )
    (comp (ref "R37")
      (value "0Ω")
      (footprint "easyedapro:R0603")
      (description "电阻类型:厚膜电阻;阻值:0Ω;精度:±1%;功率:100mW;最大工作电压:75V;")
      (fields
        (field (name "Manufacturer Part") "0402WGF0000TCE")
        (field (name "Manufacturer") "UNI-ROYAL(厚声)")
      )
      (libsource (lib "easyedapro") (part "0603WAF0000T5E"))
    )
    (comp (ref "R38")
      (value "0Ω")
      (footprint "easyedapro:R0603")
      (description "电阻类型:厚膜电阻;阻值:0Ω;精度:±1%;功率:100mW;最大工作电压:75V;")
      (fields
        (field (name "Manufacturer Part") "0402WGF0000TCE")
        (field (name "Manufacturer") "UNI-ROYAL(厚声)")
      )
      (libsource (lib "easyedapro") (part "0603WAF0000T5E"))
    )
    (comp (ref "R39")
      (value "0Ω")
      (footprint "easyedapro:R0603")
      (description "电阻类型:厚膜电阻;阻值:0Ω;精度:±1%;功率:100mW;最大工作电压:75V;")
      (fields
        (field (name "Manufacturer Part") "0402WGF0000TCE")
        (field (name "Manufacturer") "UNI-ROYAL(厚声)")
      )
      (libsource (lib "easyedapro") (part "0603WAF0000T5E"))
    )
    (comp (ref "R40")
      (value "0Ω")
      (footprint "easyedapro:R0603")
      (description "电阻类型:厚膜电阻;阻值:0Ω;精度:±1%;功率:100mW;最大工作电压:75V;")
      (fields
        (field (name "Manufacturer Part") "0402WGF0000TCE")
        (field (name "Manufacturer") "UNI-ROYAL(厚声)")
      )
      (libsource (lib "easyedapro") (part "0603WAF0000T5E"))
    )
    (comp (ref "R41")
      (value "0Ω")
      (footprint "easyedapro:R0603")
      (description "电阻类型:厚膜电阻;阻值:0Ω;精度:±1%;功率:100mW;最大工作电压:75V;")
      (fields
        (field (name "Manufacturer Part") "0402WGF0000TCE")
        (field (name "Manufacturer") "UNI-ROYAL(厚声)")
      )
      (libsource (lib "easyedapro") (part "0603WAF0000T5E"))
    )
    (comp (ref "R42")
      (value "0Ω")
      (footprint "easyedapro:R0603")
      (description "电阻类型:厚膜电阻;阻值:0Ω;精度:±1%;功率:100mW;最大工作电压:75V;")
      (fields
        (field (name "Manufacturer Part") "0402WGF0000TCE")
        (field (name "Manufacturer") "UNI-ROYAL(厚声)")
      )
      (libsource (lib "easyedapro") (part "0603WAF0000T5E"))
    )
    (comp (ref "R43")
      (value "0Ω")
      (footprint "easyedapro:R0603")
      (description "电阻类型:厚膜电阻;阻值:0Ω;精度:±1%;功率:100mW;最大工作电压:75V;")
      (fields
        (field (name "Manufacturer Part") "0402WGF0000TCE")
        (field (name "Manufacturer") "UNI-ROYAL(厚声)")
      )
      (libsource (lib "easyedapro") (part "0603WAF0000T5E"))
    )
    (comp (ref "U7")
      (value "DRV8837CDSGR")
      (footprint "easyedapro:WSON-8_L2.0-W2.0-P0.50-TL-EP")
      (description "DRV8837C 12V、1A H 桥电机驱动器")
      (fields (field (name "Manufacturer") "TI(德州仪器)"))
      (libsource (lib "easyedapro") (part "DRV8837CDSGR"))
    )
    (comp (ref "U8")
      (value "DRV8837CDSGR")
      (footprint "easyedapro:WSON-8_L2.0-W2.0-P0.50-TL-EP")
      (description "DRV8837C 12V、1A H 桥电机驱动器")
      (fields (field (name "Manufacturer") "TI(德州仪器)"))
      (libsource (lib "easyedapro") (part "DRV8837CDSGR"))
    )
    (comp (ref "D1")
      (value "USBLC6-2SC6")
      (footprint "easyedapro:SOT-23-6_L2.9-W1.6-P0.95-LS2.8-BL")
      (description "最大钳位电压:15V;击穿电压:6V;")
      (fields (field (name "Manufacturer") "UMW(友台半导体)"))
      (libsource (lib "easyedapro") (part "USBLC6-2SC6_C2687116"))
    )
    (comp (ref "R1")
      (value "4.7kΩ")
      (footprint "easyedapro:R0402")
      (description "电阻类型:厚膜电阻;阻值:4.7kΩ;精度:±5%;功率:62.5mW;最大工作电压:50V;温度系数:±100ppm/°C;")
      (fields (field (name "Manufacturer Part") "RTT02472JTH") (field (name "Manufacturer") "RALEC(旺诠)"))
      (libsource (lib "easyedapro") (part "RTT02472JTH"))
    )
    (comp (ref "R2")
      (value "4.7kΩ")
      (footprint "easyedapro:R0402")
      (description "电阻类型:厚膜电阻;阻值:4.7kΩ;精度:±5%;功率:62.5mW;最大工作电压:50V;温度系数:±100ppm/°C;")
      (fields (field (name "Manufacturer Part") "RTT02472JTH") (field (name "Manufacturer") "RALEC(旺诠)"))
      (libsource (lib "easyedapro") (part "RTT02472JTH"))
    )
    (comp (ref "U18")
      (value "SMD0805B050TF")
      (footprint "easyedapro:F0805")
      (description "耐压:6V;最大电流:100A;保持电流(Ih):500mA;跳闸电流:1A;")
      (fields (field (name "Manufacturer") "Brightking(君耀电子)"))
      (libsource (lib "easyedapro") (part "SMD0805B050TF"))
    )
    (comp (ref "USB2")
      (value "USB-TYPE-C-018")
      (footprint "easyedapro:USB-C_SMD-TYPE-C-31-M-12")
      (description "连接器类型:Type-C;标准:-;公母:母;安装方式:卧贴;触点数量:16P;端口数量:1;额定电流 - 电源:3A;工作温度范围:-25°C~+85°C;")
      (fields (field (name "Manufacturer") "DEALON(德艺隆)"))
      (libsource (lib "easyedapro") (part "USB-TYPE-C-018"))
    )
  )
  (nets
    (net (code "1") (name "3V3") (class "Default")
      (node (ref "C12") (pin "2") (pinfunction "2_2") (pintype "unspecified"))
      (node (ref "C14") (pin "2") (pinfunction "2_2") (pintype "unspecified"))
      (node (ref "C15") (pin "1") (pinfunction "1_1") (pintype "unspecified"))
      (node (ref "C16") (pin "1") (pinfunction "1_1") (pintype "unspecified"))
      (node (ref "C17") (pin "1") (pinfunction "1_1") (pintype "unspecified"))
      (node (ref "C18") (pin "1") (pinfunction "1_1") (pintype "unspecified"))
      (node (ref "C4") (pin "2") (pinfunction "2_2") (pintype "unspecified"))
      (node (ref "C7") (pin "2") (pinfunction "2_2") (pintype "unspecified"))
      (node (ref "CN1") (pin "2") (pinfunction "2_2") (pintype "unspecified"))
      (node (ref "CN2") (pin "2") (pinfunction "2_2") (pintype "unspecified"))
      (node (ref "H1") (pin "1") (pinfunction "1_1") (pintype "unspecified"))
      (node (ref "L1") (pin "2") (pinfunction "2_2") (pintype "unspecified"))
      (node (ref "L2") (pin "2") (pinfunction "2_2") (pintype "unspecified"))
      (node (ref "R3") (pin "2") (pinfunction "2_2") (pintype "input"))
      (node (ref "R32") (pin "1") (pinfunction "1_1") (pintype "input"))
      (node (ref "R33") (pin "1") (pinfunction "1_1") (pintype "input"))
      (node (ref "R47") (pin "2") (pinfunction "2_2") (pintype "input"))
      (node (ref "R52") (pin "2") (pinfunction "2_2") (pintype "input"))
      (node (ref "R53") (pin "2") (pinfunction "2_2") (pintype "input"))
      (node (ref "R58") (pin "2") (pinfunction "2_2") (pintype "input"))
      (node (ref "SW1") (pin "2") (pinfunction "2_2") (pintype "unspecified"))
      (node (ref "U1") (pin "1") (pinfunction "VBAT_1") (pintype "unspecified"))
      (node (ref "U1") (pin "24") (pinfunction "VDD_1_24") (pintype "unspecified"))
      (node (ref "U1") (pin "36") (pinfunction "VDD_2_36") (pintype "unspecified"))
      (node (ref "U1") (pin "48") (pinfunction "VDD_3_48") (pintype "unspecified"))
      (node (ref "U10") (pin "8") (pinfunction "V3_8") (pintype "unspecified"))
      (node (ref "U7") (pin "8") (pinfunction "VCC_8") (pintype "unspecified"))
      (node (ref "U8") (pin "8") (pinfunction "VCC_8") (pintype "unspecified"))
    )
    (net (code "2") (name "3V3_A") (class "Default")
      (node (ref "C19") (pin "1") (pinfunction "1_1") (pintype "unspecified"))
      (node (ref "L2") (pin "1") (pinfunction "1_1") (pintype "unspecified"))
      (node (ref "U1") (pin "9") (pinfunction "VDD_A_9") (pintype "unspecified"))
    )
    (net (code "3") (name "12V") (class "Default")
      (node (ref "R56") (pin "2") (pinfunction "2_2") (pintype "input"))
      (node (ref "U3") (pin "1") (pinfunction "1_1") (pintype "unspecified"))
      (node (ref "U4") (pin "1") (pinfunction "1_1") (pintype "unspecified"))
      (node (ref "U5") (pin "1") (pinfunction "1_1") (pintype "unspecified"))
    )
    (net (code "4") (name "12V_D") (class "Default")
      (node (ref "R11") (pin "1") (pinfunction "1_1") (pintype "input"))
      (node (ref "R53") (pin "1") (pinfunction "1_1") (pintype "input"))
      (node (ref "U1") (pin "20") (pinfunction "PB2BOOT1_20") (pintype "unspecified"))
    )
    (net (code "5") (name "D+") (class "Default")
      (node (ref "D432") (pin "3") (pinfunction "I/O2_3") (pintype "unspecified"))
      (node (ref "U10") (pin "1") (pinfunction "UD+_1") (pintype "unspecified"))
    )
    (net (code "6") (name "D-") (class "Default")
      (node (ref "D432") (pin "1") (pinfunction "I/O1_1") (pintype "unspecified"))
      (node (ref "U10") (pin "2") (pinfunction "UD-_2") (pintype "unspecified"))
    )
    (net (code "7") (name "DN") (class "Default")
      (node (ref "D1") (pin "4") (pinfunction "I/O2_4") (pintype "unspecified"))
      (node (ref "USB2") (pin "A7") (pinfunction "DN1_A7") (pintype "unspecified"))
      (node (ref "USB2") (pin "B7") (pinfunction "DN2_B7") (pintype "unspecified"))
    )
    (net (code "8") (name "DP") (class "Default")
      (node (ref "D1") (pin "6") (pinfunction "I/O1_6") (pintype "unspecified"))
      (node (ref "USB2") (pin "A6") (pinfunction "DP1_A6") (pintype "unspecified"))
      (node (ref "USB2") (pin "B6") (pinfunction "DP2_B6") (pintype "unspecified"))
    )
    (net (code "9") (name "GND") (class "Default")
      (node (ref "C10") (pin "1") (pinfunction "1_1") (pintype "unspecified"))
      (node (ref "C11") (pin "1") (pinfunction "1_1") (pintype "unspecified"))
      (node (ref "C12") (pin "1") (pinfunction "1_1") (pintype "unspecified"))
      (node (ref "C13") (pin "1") (pinfunction "1_1") (pintype "unspecified"))
      (node (ref "C14") (pin "1") (pinfunction "1_1") (pintype "unspecified"))
      (node (ref "C15") (pin "2") (pinfunction "2_2") (pintype "unspecified"))
      (node (ref "C16") (pin "2") (pinfunction "2_2") (pintype "unspecified"))
      (node (ref "C17") (pin "2") (pinfunction "2_2") (pintype "unspecified"))
      (node (ref "C18") (pin "2") (pinfunction "2_2") (pintype "unspecified"))
      (node (ref "C19") (pin "2") (pinfunction "2_2") (pintype "unspecified"))
      (node (ref "C20") (pin "2") (pinfunction "2_2") (pintype "unspecified"))
      (node (ref "C21") (pin "1") (pinfunction "1_1") (pintype "input"))
      (node (ref "C22") (pin "2") (pinfunction "2_2") (pintype "input"))
      (node (ref "C3") (pin "1") (pinfunction "1_1") (pintype "unspecified"))
      (node (ref "C4") (pin "1") (pinfunction "1_1") (pintype "unspecified"))
      (node (ref "C5") (pin "1") (pinfunction "1_1") (pintype "unspecified"))
      (node (ref "C7") (pin "1") (pinfunction "1_1") (pintype "unspecified"))
      (node (ref "C8") (pin "1") (pinfunction "1_1") (pintype "unspecified"))
      (node (ref "C9") (pin "1") (pinfunction "1_1") (pintype "unspecified"))
      (node (ref "CN1") (pin "5") (pinfunction "5_5") (pintype "unspecified"))
      (node (ref "CN2") (pin "5") (pinfunction "5_5") (pintype "unspecified"))
      (node (ref "D1") (pin "2") (pinfunction "GND_2") (pintype "unspecified"))
      (node (ref "D430") (pin "2") (pinfunction "A_2") (pintype "unspecified"))
      (node (ref "D431") (pin "2") (pinfunction "A_2") (pintype "unspecified"))
      (node (ref "D432") (pin "2") (pinfunction "GND_2") (pintype "unspecified"))
      (node (ref "H1") (pin "6") (pinfunction "6_6") (pintype "unspecified"))
      (node (ref "R1") (pin "1") (pinfunction "1_1") (pintype "input"))
      (node (ref "R19") (pin "1") (pinfunction "1_1") (pintype "unspecified"))
      (node (ref "R2") (pin "1") (pinfunction "1_1") (pintype "input"))
      (node (ref "R20") (pin "1") (pinfunction "1_1") (pintype "unspecified"))
      (node (ref "R21") (pin "1") (pinfunction "1_1") (pintype "unspecified"))
      (node (ref "R25") (pin "1") (pinfunction "1_1") (pintype "unspecified"))
      (node (ref "R26") (pin "1") (pinfunction "1_1") (pintype "unspecified"))
      (node (ref "R27") (pin "1") (pinfunction "1_1") (pintype "unspecified"))
      (node (ref "R4") (pin "1") (pinfunction "1_1") (pintype "input"))
      (node (ref "R44") (pin "2") (pinfunction "2_2") (pintype "input"))
      (node (ref "SW2") (pin "2") (pinfunction "2_2") (pintype "unspecified"))
      (node (ref "U1") (pin "23") (pinfunction "VSS_1_23") (pintype "unspecified"))
      (node (ref "U1") (pin "35") (pinfunction "VSS_2_35") (pintype "unspecified"))
      (node (ref "U1") (pin "47") (pinfunction "VSS_3_47") (pintype "unspecified"))
      (node (ref "U1") (pin "8") (pinfunction "VSS_A_8") (pintype "unspecified"))
      (node (ref "U10") (pin "3") (pinfunction "GND_3") (pintype "unspecified"))
      (node (ref "U11") (pin "4") (pinfunction "VEE_4") (pintype "unspecified"))
      (node (ref "U13") (pin "2") (pinfunction "GND_2") (pintype "unspecified"))
      (node (ref "U14") (pin "1") (pinfunction "K_1") (pintype "unspecified"))
      (node (ref "U15") (pin "1") (pinfunction "K_1") (pintype "unspecified"))
      (node (ref "U3") (pin "2") (pinfunction "2_2") (pintype "unspecified"))
      (node (ref "U7") (pin "4") (pinfunction "GND_4") (pintype "unspecified"))
      (node (ref "U7") (pin "9") (pinfunction "PAD_9") (pintype "unspecified"))
      (node (ref "U8") (pin "4") (pinfunction "GND_4") (pintype "unspecified"))
      (node (ref "U8") (pin "9") (pinfunction "PAD_9") (pintype "unspecified"))
      (node (ref "USB1") (pin "4") (pinfunction "4_4") (pintype "unspecified"))
      (node (ref "USB1") (pin "5") (pinfunction "5_5") (pintype "unspecified"))
      (node (ref "USB1") (pin "6") (pinfunction "6_6") (pintype "unspecified"))
      (node (ref "USB2") (pin "0") (pinfunction "SH_0") (pintype "unspecified"))
      (node (ref "USB2") (pin "1") (pinfunction "SH_1") (pintype "unspecified"))
      (node (ref "USB2") (pin "2") (pinfunction "SH_2") (pintype "unspecified"))
      (node (ref "USB2") (pin "3") (pinfunction "SH_3") (pintype "unspecified"))
      (node (ref "USB2") (pin "A1") (pinfunction "GND_A1") (pintype "unspecified"))
      (node (ref "USB2") (pin "A12") (pinfunction "GND_A12") (pintype "unspecified"))
      (node (ref "USB2") (pin "B1") (pinfunction "GND_B1") (pintype "unspecified"))
      (node (ref "USB2") (pin "B12") (pinfunction "GND_B12") (pintype "unspecified"))
      (node (ref "X1") (pin "2") (pinfunction "2_2") (pintype "input"))
      (node (ref "X1") (pin "4") (pinfunction "4_4") (pintype "input"))
    )
    (net (code "10") (name "LED1_D") (class "Default")
      (node (ref "R12") (pin "1") (pinfunction "1_1") (pintype "input"))
      (node (ref "R32") (pin "2") (pinfunction "2_2") (pintype "input"))
      (node (ref "U1") (pin "18") (pinfunction "PB0ADC12_IN8TIM3_CH3_18") (pintype "unspecified"))
    )
    (net (code "11") (name "LED1_DIM") (class "Default")
      (node (ref "R16") (pin "1") (pinfunction "1_1") (pintype "input"))
      (node (ref "R45") (pin "1") (pinfunction "1_1") (pintype "input"))
      (node (ref "U1") (pin "30") (pinfunction "PA9USART1_TXTIM1_CH2_30") (pintype "unspecified"))
    )
    (net (code "12") (name "LED2_D") (class "Default")
      (node (ref "R13") (pin "1") (pinfunction "1_1") (pintype "input"))
      (node (ref "R33") (pin "2") (pinfunction "2_2") (pintype "input"))
      (node (ref "U1") (pin "19") (pinfunction "PB1ADC12_IN9TIM3_CH4_19") (pintype "unspecified"))
    )
    (net (code "13") (name "LED2_DIM") (class "Default")
      (node (ref "R17") (pin "1") (pinfunction "1_1") (pintype "input"))
      (node (ref "U1") (pin "29") (pinfunction "PA8USART1_CKTIM1_CH1MCO_29") (pintype "unspecified"))
    )
    (net (code "14") (name "M1_A") (class "Default")
      (node (ref "R34") (pin "1") (pinfunction "1_1") (pintype "input"))
      (node (ref "U1") (pin "16") (pinfunction "PA6SPI1_MISOADC12_IN6TIM3_CH1_16") (pintype "unspecified"))
    )
    (net (code "15") (name "M1_B") (class "Default")
      (node (ref "R35") (pin "1") (pinfunction "1_1") (pintype "input"))
      (node (ref "U1") (pin "17") (pinfunction "PA7SPI1_MOSIADC12_IN7TIM3_CH2_17") (pintype "unspecified"))
    )
    (net (code "16") (name "M1_EN") (class "Default")
      (node (ref "R38") (pin "1") (pinfunction "1_1") (pintype "input"))
      (node (ref "U1") (pin "46") (pinfunction "PB9TIM4_CH4_46") (pintype "unspecified"))
    )
    (net (code "17") (name "M1_IN1") (class "Default")
      (node (ref "R39") (pin "1") (pinfunction "1_1") (pintype "input"))
      (node (ref "U1") (pin "10") (pinfunction "PA0_WKUPUSART2_CTSADC12_IN0TIM2_CH1_ETR_10") (pintype "unspecified"))
    )
    (net (code "18") (name "M1_IN2") (class "Default")
      (node (ref "R40") (pin "1") (pinfunction "1_1") (pintype "input"))
      (node (ref "U1") (pin "11") (pinfunction "PA1USART2_RTSADC12_IN1TIM2_CH2_11") (pintype "unspecified"))
    )
    (net (code "19") (name "M2_A") (class "Default")
      (node (ref "R36") (pin "1") (pinfunction "1_1") (pintype "input"))
      (node (ref "U1") (pin "42") (pinfunction "PB6I2C1_SCLTIM4_CH1_42") (pintype "unspecified"))
    )
    (net (code "20") (name "M2_B") (class "Default")
      (node (ref "R37") (pin "1") (pinfunction "1_1") (pintype "input"))
      (node (ref "U1") (pin "43") (pinfunction "PB7I2C1_SDATIM4_CH2_43") (pintype "unspecified"))
    )
    (net (code "21") (name "M2_EN") (class "Default")
      (node (ref "R41") (pin "1") (pinfunction "1_1") (pintype "input"))
      (node (ref "U1") (pin "38") (pinfunction "PA15JTDI_38") (pintype "unspecified"))
    )
    (net (code "22") (name "M2_IN1") (class "Default")
      (node (ref "R42") (pin "1") (pinfunction "1_1") (pintype "input"))
      (node (ref "U1") (pin "13") (pinfunction "PA3USART2_RXADC12_IN3TIM2_CH4_13") (pintype "unspecified"))
    )
    (net (code "23") (name "M2_IN2") (class "Default")
      (node (ref "R43") (pin "1") (pinfunction "1_1") (pintype "input"))
      (node (ref "U1") (pin "12") (pinfunction "PA2USART2_TXADC12_IN2TIM2_CH3_12") (pintype "unspecified"))
    )
    (net (code "24") (name "Net-(CN1-Pad3)") (class "Default")
      (node (ref "CN1") (pin "3") (pinfunction "3_3") (pintype "unspecified"))
      (node (ref "R34") (pin "2") (pinfunction "2_2") (pintype "input"))
    )
    (net (code "25") (name "Net-(CN1-Pad4)") (class "Default")
      (node (ref "CN1") (pin "4") (pinfunction "4_4") (pintype "unspecified"))
      (node (ref "R35") (pin "2") (pinfunction "2_2") (pintype "input"))
    )
    (net (code "26") (name "Net-(CN2-Pad3)") (class "Default")
      (node (ref "CN2") (pin "3") (pinfunction "3_3") (pintype "unspecified"))
      (node (ref "R36") (pin "2") (pinfunction "2_2") (pintype "input"))
    )
    (net (code "27") (name "Net-(CN2-Pad4)") (class "Default")
      (node (ref "CN2") (pin "4") (pinfunction "4_4") (pintype "unspecified"))
      (node (ref "R37") (pin "2") (pinfunction "2_2") (pintype "input"))
    )
    (net (code "28") (name "Net-(D430-C)") (class "Default")
      (node (ref "C8") (pin "2") (pinfunction "2_2") (pintype "unspecified"))
      (node (ref "D430") (pin "1") (pinfunction "C_1") (pintype "unspecified"))
      (node (ref "R16") (pin "2") (pinfunction "2_2") (pintype "input"))
      (node (ref "U11") (pin "3") (pinfunction "IN_A+_3") (pintype "unspecified"))
    )
    (net (code "29") (name "Net-(D431-C)") (class "Default")
      (node (ref "C9") (pin "2") (pinfunction "2_2") (pintype "unspecified"))
      (node (ref "D431") (pin "1") (pinfunction "C_1") (pintype "unspecified"))
      (node (ref "R17") (pin "2") (pinfunction "2_2") (pintype "input"))
      (node (ref "U11") (pin "5") (pinfunction "IN_B+_5") (pintype "unspecified"))
    )
    (net (code "30") (name "Net-(D432-I{slash}O1-Pad6)") (class "Default")
      (node (ref "D432") (pin "6") (pinfunction "I/O1_6") (pintype "unspecified"))
      (node (ref "USB1") (pin "2") (pinfunction "2_2") (pintype "unspecified"))
    )
    (net (code "31") (name "Net-(D432-I{slash}O2-Pad4)") (class "Default")
      (node (ref "D432") (pin "4") (pinfunction "I/O2_4") (pintype "unspecified"))
      (node (ref "USB1") (pin "3") (pinfunction "3_3") (pintype "unspecified"))
    )
    (net (code "32") (name "Net-(D432-VBUS)") (class "Default")
      (node (ref "D432") (pin "5") (pinfunction "VBUS_5") (pintype "unspecified"))
      (node (ref "U16") (pin "2") (pinfunction "2_2") (pintype "unspecified"))
      (node (ref "USB1") (pin "1") (pinfunction "1_1") (pintype "unspecified"))
    )
    (net (code "33") (name "Net-(Q1-D-Pad2)") (class "Default")
      (node (ref "Q1") (pin "2") (pinfunction "D_2") (pintype "unspecified"))
      (node (ref "Q1") (pin "4") (pinfunction "D_4") (pintype "unspecified"))
      (node (ref "U4") (pin "2") (pinfunction "2_2") (pintype "unspecified"))
    )
    (net (code "34") (name "Net-(Q1-G)") (class "Default")
      (node (ref "Q1") (pin "1") (pinfunction "G_1") (pintype "unspecified"))
      (node (ref "U11") (pin "1") (pinfunction "OUT_A_1") (pintype "output"))
    )
    (net (code "35") (name "Net-(Q1-S)") (class "Default")
      (node (ref "Q1") (pin "3") (pinfunction "S_3") (pintype "unspecified"))
      (node (ref "R19") (pin "2") (pinfunction "2_2") (pintype "unspecified"))
      (node (ref "R20") (pin "2") (pinfunction "2_2") (pintype "unspecified"))
      (node (ref "R21") (pin "2") (pinfunction "2_2") (pintype "unspecified"))
      (node (ref "U11") (pin "2") (pinfunction "IN_A-_2") (pintype "unspecified"))
    )
    (net (code "36") (name "Net-(Q2-D-Pad2)") (class "Default")
      (node (ref "Q2") (pin "2") (pinfunction "D_2") (pintype "unspecified"))
      (node (ref "Q2") (pin "4") (pinfunction "D_4") (pintype "unspecified"))
      (node (ref "U5") (pin "2") (pinfunction "2_2") (pintype "unspecified"))
    )
    (net (code "37") (name "Net-(Q2-G)") (class "Default")
      (node (ref "Q2") (pin "1") (pinfunction "G_1") (pintype "unspecified"))
      (node (ref "U11") (pin "7") (pinfunction "OUT_B_7") (pintype "output"))
    )
    (net (code "38") (name "Net-(Q2-S)") (class "Default")
      (node (ref "Q2") (pin "3") (pinfunction "S_3") (pintype "unspecified"))
      (node (ref "R25") (pin "2") (pinfunction "2_2") (pintype "unspecified"))
      (node (ref "R26") (pin "2") (pinfunction "2_2") (pintype "unspecified"))
      (node (ref "R27") (pin "2") (pinfunction "2_2") (pintype "unspecified"))
      (node (ref "U11") (pin "6") (pinfunction "IN_B-_6") (pintype "unspecified"))
    )
    (net (code "39") (name "Net-(R11-Pad2)") (class "Default")
      (node (ref "R11") (pin "2") (pinfunction "2_2") (pintype "input"))
      (node (ref "U3") (pin "3") (pinfunction "3_3") (pintype "unspecified"))
    )
    (net (code "40") (name "Net-(R12-Pad2)") (class "Default")
      (node (ref "R12") (pin "2") (pinfunction "2_2") (pintype "input"))
      (node (ref "U4") (pin "3") (pinfunction "3_3") (pintype "unspecified"))
    )
    (net (code "41") (name "Net-(R13-Pad2)") (class "Default")
      (node (ref "R13") (pin "2") (pinfunction "2_2") (pintype "input"))
      (node (ref "U5") (pin "3") (pinfunction "3_3") (pintype "unspecified"))
    )
    (net (code "42") (name "Net-(U1-BOOT0)") (class "Default")
      (node (ref "R44") (pin "1") (pinfunction "1_1") (pintype "input"))
      (node (ref "SW1") (pin "1") (pinfunction "1_1") (pintype "unspecified"))
      (node (ref "U1") (pin "44") (pinfunction "BOOT0_44") (pintype "unspecified"))
    )
    (net (code "43") (name "Net-(U1-NRST)") (class "Default")
      (node (ref "C20") (pin "1") (pinfunction "1_1") (pintype "unspecified"))
      (node (ref "R47") (pin "1") (pinfunction "1_1") (pintype "input"))
      (node (ref "SW2") (pin "1") (pinfunction "1_1") (pintype "unspecified"))
      (node (ref "U1") (pin "7") (pinfunction "NRST_7") (pintype "unspecified"))
    )
    (net (code "44") (name "Net-(U1-PA10USART1_RXTIM1_CH3)") (class "Default")
      (node (ref "R46") (pin "1") (pinfunction "1_1") (pintype "input"))
      (node (ref "U1") (pin "31") (pinfunction "PA10USART1_RXTIM1_CH3_31") (pintype "unspecified"))
    )
    (net (code "45") (name "Net-(U1-PA11USART1_CTSCAN_RXTIM1_CH4USBDM)") (class "Default")
      (node (ref "R49") (pin "1") (pinfunction "1_1") (pintype "input"))
      (node (ref "U1") (pin "32") (pinfunction "PA11USART1_CTSCAN_RXTIM1_CH4USBDM_32") (pintype "unspecified"))
    )
    (net (code "46") (name "Net-(U1-PA12USART1_RTSCAN_TXTIM1_ETRUSBDP)") (class "Default")
      (node (ref "R50") (pin "1") (pinfunction "1_1") (pintype "input"))
      (node (ref "R52") (pin "1") (pinfunction "1_1") (pintype "input"))
      (node (ref "U1") (pin "33") (pinfunction "PA12USART1_RTSCAN_TXTIM1_ETRUSBDP_33") (pintype "unspecified"))
    )
    (net (code "47") (name "Net-(U7-IN1)") (class "Default")
      (node (ref "R39") (pin "2") (pinfunction "2_2") (pintype "input"))
      (node (ref "U7") (pin "6") (pinfunction "IN1_6") (pintype "unspecified"))
    )
    (net (code "48") (name "Net-(U7-IN2)") (class "Default")
      (node (ref "R40") (pin "2") (pinfunction "2_2") (pintype "input"))
      (node (ref "U7") (pin "5") (pinfunction "IN2_5") (pintype "unspecified"))
    )
    (net (code "49") (name "Net-(U7-NSLEEP)") (class "Default")
      (node (ref "R38") (pin "2") (pinfunction "2_2") (pintype "input"))
      (node (ref "U7") (pin "7") (pinfunction "NSLEEP_7") (pintype "unspecified"))
    )
    (net (code "50") (name "Net-(U7-OUT1)") (class "Default")
      (node (ref "CN1") (pin "1") (pinfunction "1_1") (pintype "unspecified"))
      (node (ref "U7") (pin "2") (pinfunction "OUT1_2") (pintype "unspecified"))
    )
    (net (code "51") (name "Net-(U7-OUT2)") (class "Default")
      (node (ref "CN1") (pin "6") (pinfunction "6_6") (pintype "unspecified"))
      (node (ref "U7") (pin "3") (pinfunction "OUT2_3") (pintype "unspecified"))
    )
    (net (code "52") (name "Net-(U8-IN1)") (class "Default")
      (node (ref "R42") (pin "2") (pinfunction "2_2") (pintype "input"))
      (node (ref "U8") (pin "6") (pinfunction "IN1_6") (pintype "unspecified"))
    )
    (net (code "53") (name "Net-(U8-IN2)") (class "Default")
      (node (ref "R43") (pin "2") (pinfunction "2_2") (pintype "input"))
      (node (ref "U8") (pin "5") (pinfunction "IN2_5") (pintype "unspecified"))
    )
    (net (code "54") (name "Net-(U8-NSLEEP)") (class "Default")
      (node (ref "R41") (pin "2") (pinfunction "2_2") (pintype "input"))
      (node (ref "U8") (pin "7") (pinfunction "NSLEEP_7") (pintype "unspecified"))
    )
    (net (code "55") (name "Net-(U8-OUT1)") (class "Default")
      (node (ref "CN2") (pin "1") (pinfunction "1_1") (pintype "unspecified"))
      (node (ref "U8") (pin "2") (pinfunction "OUT1_2") (pintype "unspecified"))
    )
    (net (code "56") (name "Net-(U8-OUT2)") (class "Default")
      (node (ref "CN2") (pin "6") (pinfunction "6_6") (pintype "unspecified"))
      (node (ref "U8") (pin "3") (pinfunction "OUT2_3") (pintype "unspecified"))
    )
    (net (code "57") (name "Net-(U10-RTS#)") (class "Default")
      (node (ref "R10") (pin "2") (pinfunction "2_2") (pintype "input"))
      (node (ref "U10") (pin "4") (pinfunction "RTS#_4") (pintype "unspecified"))
    )
    (net (code "58") (name "Net-(U10-RXD)") (class "Default")
      (node (ref "R6") (pin "2") (pinfunction "2_2") (pintype "input"))
      (node (ref "U10") (pin "7") (pinfunction "RXD_7") (pintype "unspecified"))
    )
    (net (code "59") (name "Net-(U10-TXD)") (class "Default")
      (node (ref "R8") (pin "2") (pinfunction "2_2") (pintype "input"))
      (node (ref "U10") (pin "6") (pinfunction "TXD_6") (pintype "unspecified"))
    )
    (net (code "60") (name "Net-(U13-FB)") (class "Default")
      (node (ref "R3") (pin "1") (pinfunction "1_1") (pintype "input"))
      (node (ref "R4") (pin "2") (pinfunction "2_2") (pintype "input"))
      (node (ref "U13") (pin "5") (pinfunction "FB_5") (pintype "unspecified"))
    )
    (net (code "61") (name "Net-(U13-SW)") (class "Default")
      (node (ref "L1") (pin "1") (pinfunction "1_1") (pintype "unspecified"))
      (node (ref "U13") (pin "3") (pinfunction "SW_3") (pintype "unspecified"))
    )
    (net (code "62") (name "Net-(U14-A)") (class "Default")
      (node (ref "R56") (pin "1") (pinfunction "1_1") (pintype "input"))
      (node (ref "U14") (pin "2") (pinfunction "A_2") (pintype "unspecified"))
    )
    (net (code "63") (name "Net-(U15-A)") (class "Default")
      (node (ref "R54") (pin "1") (pinfunction "1_1") (pintype "input"))
      (node (ref "U15") (pin "2") (pinfunction "A_2") (pintype "unspecified"))
    )
    (net (code "64") (name "Net-(U17-A)") (class "Default")
      (node (ref "R58") (pin "1") (pinfunction "1_1") (pintype "input"))
      (node (ref "U17") (pin "2") (pinfunction "A_2") (pintype "unspecified"))
    )
    (net (code "65") (name "Net-(USB2-CC1)") (class "Default")
      (node (ref "R2") (pin "2") (pinfunction "2_2") (pintype "input"))
      (node (ref "USB2") (pin "A5") (pinfunction "CC1_A5") (pintype "unspecified"))
    )
    (net (code "66") (name "Net-(USB2-CC2)") (class "Default")
      (node (ref "R1") (pin "2") (pinfunction "2_2") (pintype "input"))
      (node (ref "USB2") (pin "B5") (pinfunction "CC2_B5") (pintype "unspecified"))
    )
    (net (code "67") (name "OSC_IN") (class "Default")
      (node (ref "C21") (pin "2") (pinfunction "2_2") (pintype "input"))
      (node (ref "U1") (pin "5") (pinfunction "PD0-OSC_IN_5") (pintype "unspecified"))
      (node (ref "X1") (pin "3") (pinfunction "3_3") (pintype "input"))
    )
    (net (code "68") (name "OSC_OUT") (class "Default")
      (node (ref "C22") (pin "1") (pinfunction "1_1") (pintype "input"))
      (node (ref "U1") (pin "6") (pinfunction "PD1-OSC_OUT_6") (pintype "unspecified"))
      (node (ref "X1") (pin "1") (pinfunction "1_1") (pintype "input"))
    )
    (net (code "69") (name "RTS") (class "Default")
      (node (ref "R10") (pin "1") (pinfunction "1_1") (pintype "input"))
      (node (ref "U1") (pin "26") (pinfunction "PB13SPI2_SCKUSART3_CTSTIM1_CH1N_26") (pintype "unspecified"))
    )
    (net (code "70") (name "STATUS") (class "Default")
      (node (ref "U1") (pin "25") (pinfunction "PB12SPI2_NSSI2C2_SMBAUSART3_CKTIM1_BKIN_25") (pintype "unspecified"))
      (node (ref "U17") (pin "1") (pinfunction "K_1") (pintype "unspecified"))
    )
    (net (code "71") (name "SWDCK") (class "Default")
      (node (ref "H1") (pin "2") (pinfunction "2_2") (pintype "unspecified"))
      (node (ref "U1") (pin "37") (pinfunction "PA14JTCKSWCLK_37") (pintype "unspecified"))
    )
    (net (code "72") (name "SWDIO") (class "Default")
      (node (ref "H1") (pin "3") (pinfunction "3_3") (pintype "unspecified"))
      (node (ref "U1") (pin "34") (pinfunction "PA13JTMSSWDIO_34") (pintype "unspecified"))
    )
    (net (code "73") (name "UART1_RXD") (class "Default")
      (node (ref "H1") (pin "4") (pinfunction "4_4") (pintype "unspecified"))
      (node (ref "R46") (pin "2") (pinfunction "2_2") (pintype "input"))
    )
    (net (code "74") (name "UART1_TXD") (class "Default")
      (node (ref "H1") (pin "5") (pinfunction "5_5") (pintype "unspecified"))
      (node (ref "R45") (pin "2") (pinfunction "2_2") (pintype "input"))
    )
    (net (code "75") (name "USB_DN") (class "Default")
      (node (ref "D1") (pin "3") (pinfunction "I/O2_3") (pintype "unspecified"))
      (node (ref "R49") (pin "2") (pinfunction "2_2") (pintype "input"))
    )
    (net (code "76") (name "USB_DP") (class "Default")
      (node (ref "D1") (pin "1") (pinfunction "I/O1_1") (pintype "unspecified"))
      (node (ref "R50") (pin "2") (pinfunction "2_2") (pintype "input"))
    )
    (net (code "77") (name "U_RX") (class "Default")
      (node (ref "R6") (pin "1") (pinfunction "1_1") (pintype "input"))
      (node (ref "U1") (pin "21") (pinfunction "PB10I2C2_SCLUSART3_TX_21") (pintype "unspecified"))
    )
    (net (code "78") (name "U_TX") (class "Default")
      (node (ref "R8") (pin "1") (pinfunction "1_1") (pintype "input"))
      (node (ref "U1") (pin "22") (pinfunction "PB11I2C2_SDAUSART3_RX-_22") (pintype "unspecified"))
    )
    (net (code "79") (name "VBUS") (class "Default")
      (node (ref "D1") (pin "5") (pinfunction "VBUS_5") (pintype "unspecified"))
      (node (ref "U18") (pin "2") (pinfunction "2_2") (pintype "unspecified"))
      (node (ref "USB2") (pin "A4") (pinfunction "VBUS_A4") (pintype "unspecified"))
      (node (ref "USB2") (pin "A9") (pinfunction "VBUS_A9") (pintype "unspecified"))
      (node (ref "USB2") (pin "B4") (pinfunction "VBUS_B4") (pintype "unspecified"))
      (node (ref "USB2") (pin "B9") (pinfunction "VBUS_B9") (pintype "unspecified"))
    )
    (net (code "80") (name "VUSB") (class "Default")
      (node (ref "C10") (pin "2") (pinfunction "2_2") (pintype "unspecified"))
      (node (ref "C11") (pin "2") (pinfunction "2_2") (pintype "unspecified"))
      (node (ref "C13") (pin "2") (pinfunction "2_2") (pintype "unspecified"))
      (node (ref "C3") (pin "2") (pinfunction "2_2") (pintype "unspecified"))
      (node (ref "C5") (pin "2") (pinfunction "2_2") (pintype "unspecified"))
      (node (ref "R54") (pin "2") (pinfunction "2_2") (pintype "input"))
      (node (ref "U10") (pin "5") (pinfunction "VCC_5") (pintype "unspecified"))
      (node (ref "U11") (pin "8") (pinfunction "VCC_8") (pintype "unspecified"))
      (node (ref "U13") (pin "1") (pinfunction "RUN_1") (pintype "unspecified"))
      (node (ref "U13") (pin "4") (pinfunction "VIN_4") (pintype "unspecified"))
      (node (ref "U16") (pin "1") (pinfunction "1_1") (pintype "unspecified"))
      (node (ref "U18") (pin "1") (pinfunction "1_1") (pintype "unspecified"))
      (node (ref "U7") (pin "1") (pinfunction "VMIN_1") (pintype "unspecified"))
      (node (ref "U8") (pin "1") (pinfunction "VMIN_1") (pintype "unspecified"))
    )
    (net (code "81") (name "unconnected-(U1-PA4SPI1_NSSUSART2_CKADC12_IN4-Pad14)") (class "Default")
      (node (ref "U1") (pin "14") (pinfunction "PA4SPI1_NSSUSART2_CKADC12_IN4_14") (pintype "unspecified"))
    )
    (net (code "82") (name "unconnected-(U1-PA5SPI1_SCKADC12_IN5-Pad15)") (class "Default")
      (node (ref "U1") (pin "15") (pinfunction "PA5SPI1_SCKADC12_IN5_15") (pintype "unspecified"))
    )
    (net (code "83") (name "unconnected-(U1-PB3JTDO-Pad39)") (class "Default")
      (node (ref "U1") (pin "39") (pinfunction "PB3JTDO_39") (pintype "unspecified"))
    )
    (net (code "84") (name "unconnected-(U1-PB4NJTRST-Pad40)") (class "Default")
      (node (ref "U1") (pin "40") (pinfunction "PB4NJTRST_40") (pintype "unspecified"))
    )
    (net (code "85") (name "unconnected-(U1-PB5I2C1_SMBA-Pad41)") (class "Default")
      (node (ref "U1") (pin "41") (pinfunction "PB5I2C1_SMBA_41") (pintype "unspecified"))
    )
    (net (code "86") (name "unconnected-(U1-PB8TIM4_CH3-Pad45)") (class "Default")
      (node (ref "U1") (pin "45") (pinfunction "PB8TIM4_CH3_45") (pintype "unspecified"))
    )
    (net (code "87") (name "unconnected-(U1-PB14SPI2_MISOUSART3_RTSTIM1_CH2N-Pad27)") (class "Default")
      (node (ref "U1") (pin "27") (pinfunction "PB14SPI2_MISOUSART3_RTSTIM1_CH2N_27") (pintype "unspecified"))
    )
    (net (code "88") (name "unconnected-(U1-PB15SPI2_MOSITIM1_CH3N-Pad28)") (class "Default")
      (node (ref "U1") (pin "28") (pinfunction "PB15SPI2_MOSITIM1_CH3N_28") (pintype "unspecified"))
    )
    (net (code "89") (name "unconnected-(U1-PC13-TAMPER-RTC-Pad2)") (class "Default")
      (node (ref "U1") (pin "2") (pinfunction "PC13-TAMPER-RTC_2") (pintype "unspecified"))
    )
    (net (code "90") (name "unconnected-(U1-PC14-OSC32_IN-Pad3)") (class "Default")
      (node (ref "U1") (pin "3") (pinfunction "PC14-OSC32_IN_3") (pintype "unspecified"))
    )
    (net (code "91") (name "unconnected-(U1-PC15-OSC32_OUT-Pad4)") (class "Default")
      (node (ref "U1") (pin "4") (pinfunction "PC15-OSC32_OUT_4") (pintype "unspecified"))
    )
    (net (code "92") (name "unconnected-(USB2-SBU1-PadA8)") (class "Default")
      (node (ref "USB2") (pin "A8") (pinfunction "SBU1_A8") (pintype "unspecified+no_connect"))
    )
    (net (code "93") (name "unconnected-(USB2-SBU2-PadB8)") (class "Default")
      (node (ref "USB2") (pin "B8") (pinfunction "SBU2_B8") (pintype "unspecified+no_connect"))
    )
  )
)
